# 15fpga.net
KiCad netlist of a schematic drawn in Altium Designer
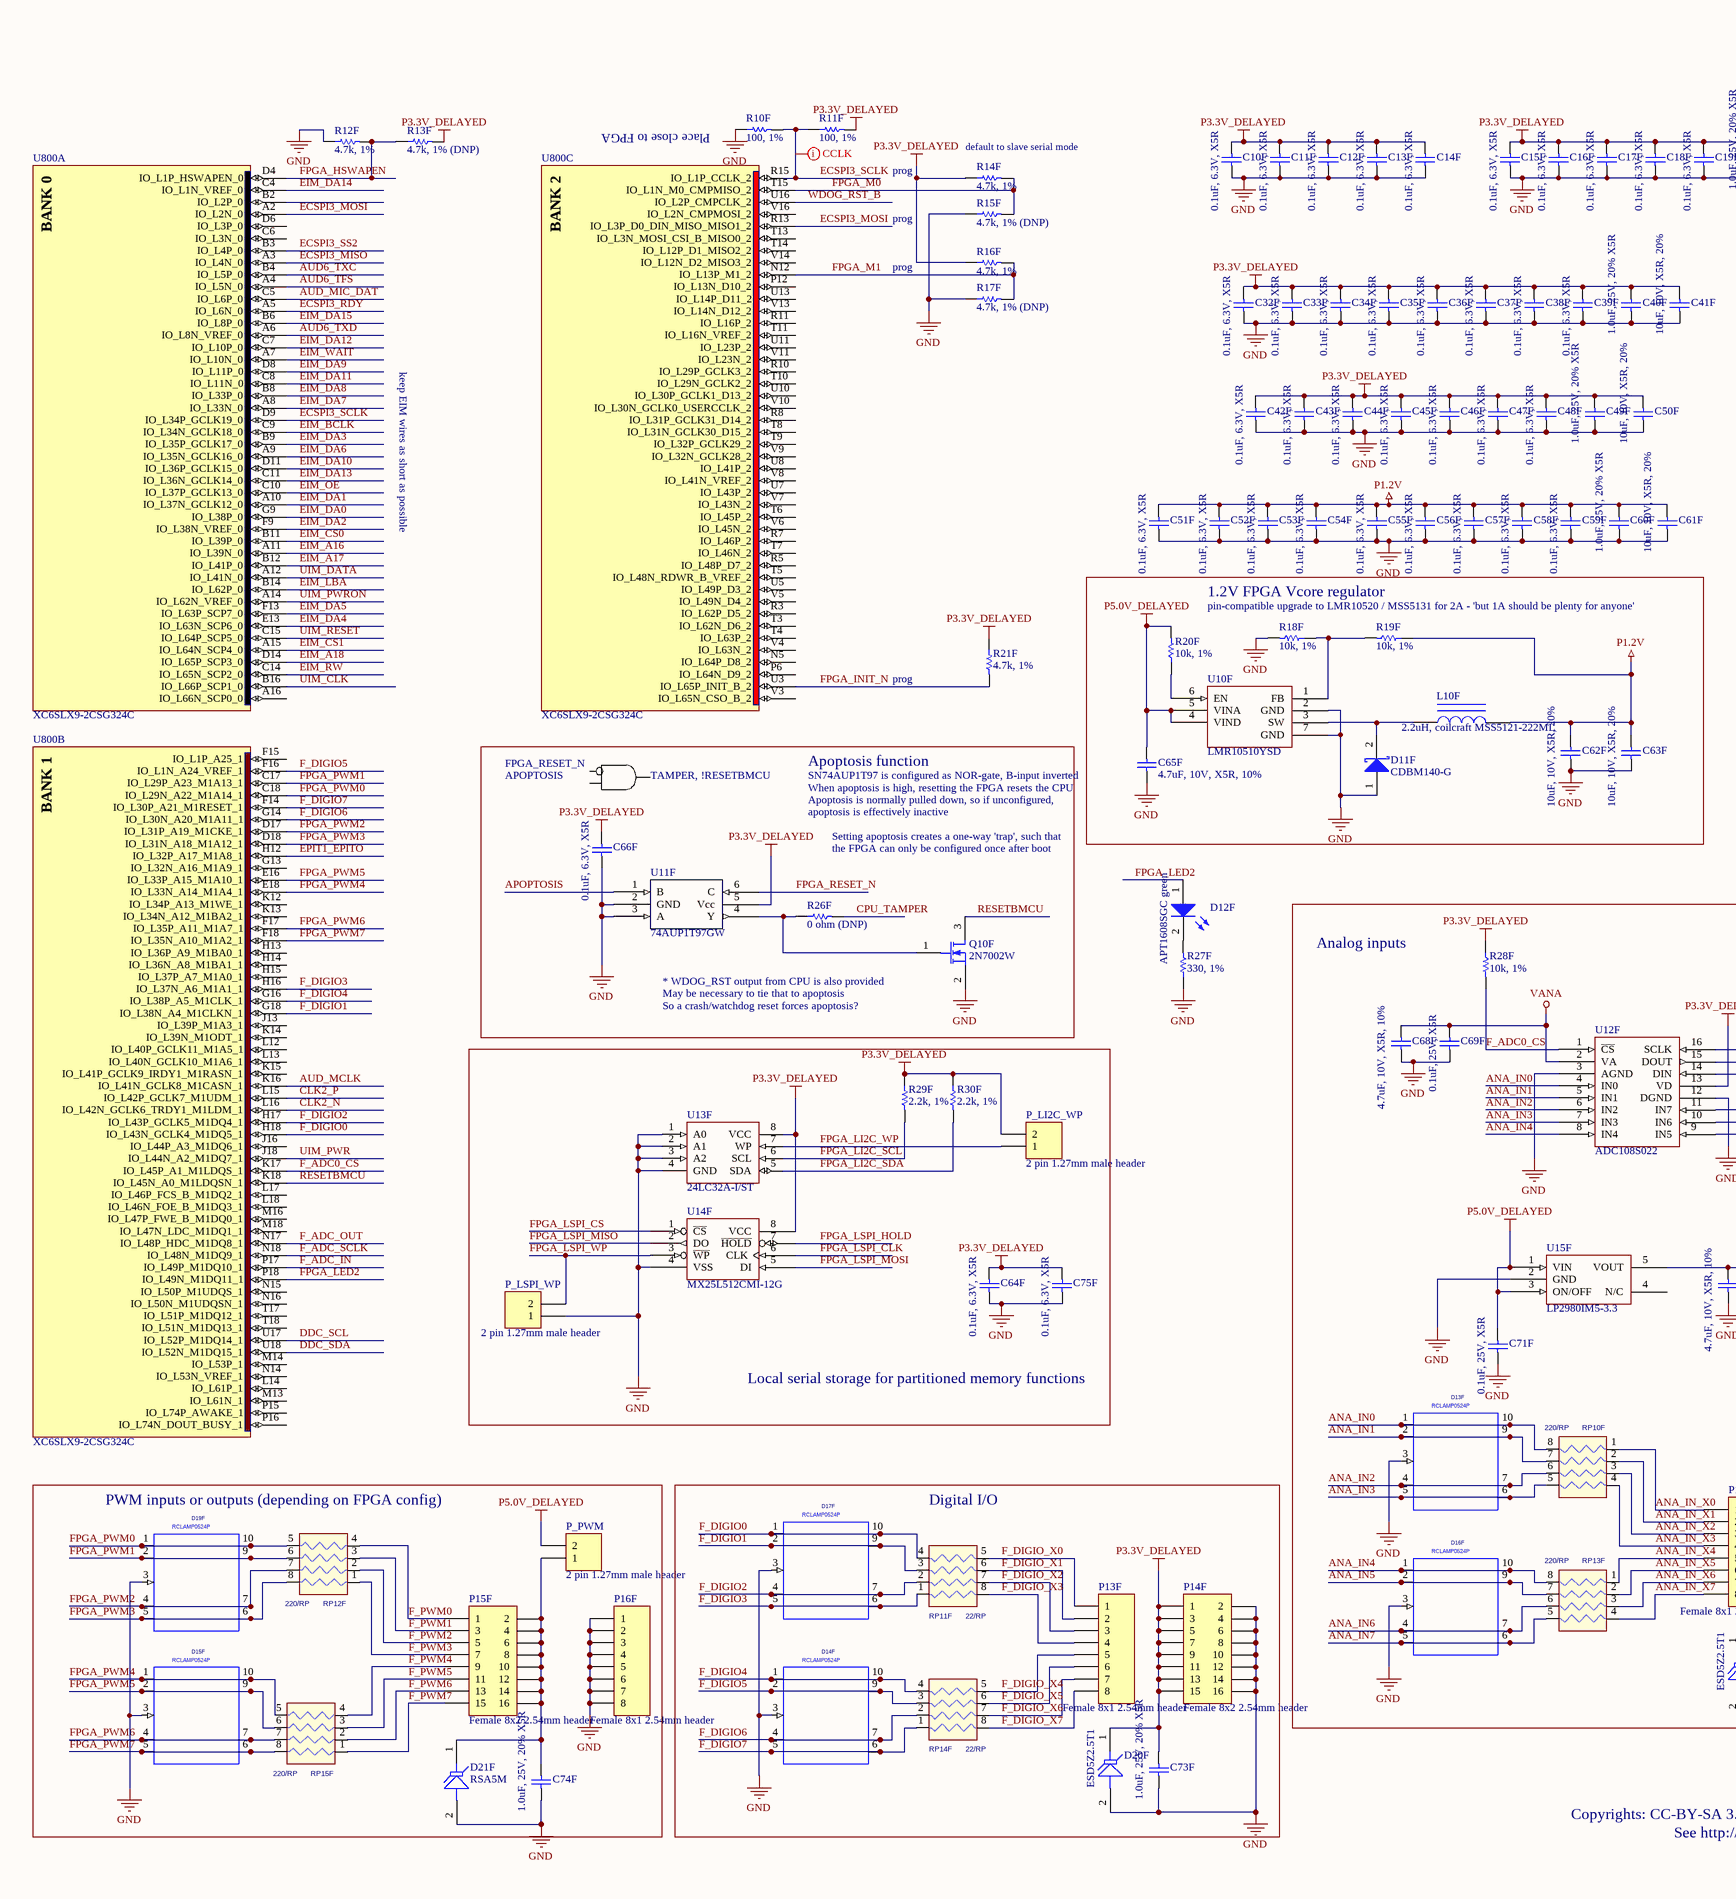
[diagram p0: 15fpga.SchDoc, left]
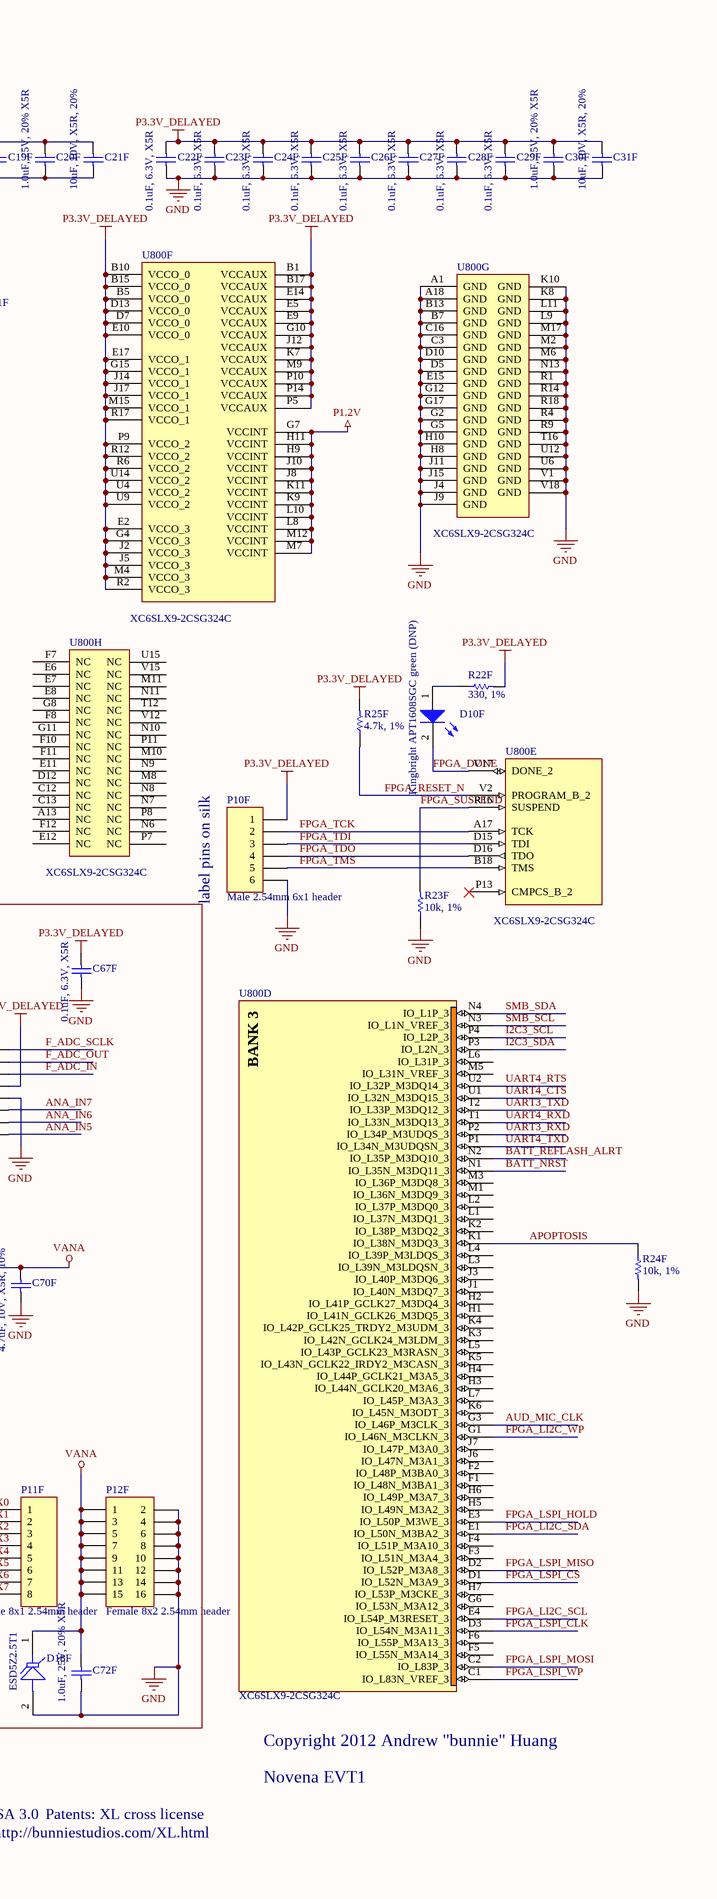
[diagram p1: 15fpga.SchDoc, right]

(export (version "E")
  (design (tool "Eeschema 10.0.6"))
  (components
    (comp (ref "C10F")
      (value "0.1uF, 6.3V, X5R")
      (footprint "CAPC0603N_B")
      (description "Capacitor (Semiconductor SIM Model)")
      (fields (field (name "PUBLISHER") "Altium Limited"))
      (libsource (lib "Miscellaneous Devices") (part "Cap Semi"))
    )
    (comp (ref "C11F")
      (value "0.1uF, 6.3V, X5R")
      (footprint "CAPC0603N_B")
      (description "Capacitor (Semiconductor SIM Model)")
      (fields (field (name "PUBLISHER") "Altium Limited"))
      (libsource (lib "Miscellaneous Devices") (part "Cap Semi"))
    )
    (comp (ref "C12F")
      (value "0.1uF, 6.3V, X5R")
      (footprint "CAPC0603N_B")
      (description "Capacitor (Semiconductor SIM Model)")
      (fields (field (name "PUBLISHER") "Altium Limited"))
      (libsource (lib "Miscellaneous Devices") (part "Cap Semi"))
    )
    (comp (ref "C13F")
      (value "0.1uF, 6.3V, X5R")
      (footprint "CAPC0603N_B")
      (description "Capacitor (Semiconductor SIM Model)")
      (fields (field (name "PUBLISHER") "Altium Limited"))
      (libsource (lib "Miscellaneous Devices") (part "Cap Semi"))
    )
    (comp (ref "C14F")
      (value "0.1uF, 6.3V, X5R")
      (footprint "CAPC0603N_B")
      (description "Capacitor (Semiconductor SIM Model)")
      (fields (field (name "PUBLISHER") "Altium Limited"))
      (libsource (lib "Miscellaneous Devices") (part "Cap Semi"))
    )
    (comp (ref "C15F")
      (value "0.1uF, 6.3V, X5R")
      (footprint "CAPC0603N_B")
      (description "Capacitor (Semiconductor SIM Model)")
      (fields (field (name "PUBLISHER") "Altium Limited"))
      (libsource (lib "Miscellaneous Devices") (part "Cap Semi"))
    )
    (comp (ref "C16F")
      (value "0.1uF, 6.3V, X5R")
      (footprint "CAPC0603N_B")
      (description "Capacitor (Semiconductor SIM Model)")
      (fields (field (name "PUBLISHER") "Altium Limited"))
      (libsource (lib "Miscellaneous Devices") (part "Cap Semi"))
    )
    (comp (ref "C17F")
      (value "0.1uF, 6.3V, X5R")
      (footprint "CAPC0603N_B")
      (description "Capacitor (Semiconductor SIM Model)")
      (fields (field (name "PUBLISHER") "Altium Limited"))
      (libsource (lib "Miscellaneous Devices") (part "Cap Semi"))
    )
    (comp (ref "C18F")
      (value "0.1uF, 6.3V, X5R")
      (footprint "CAPC0603N_B")
      (description "Capacitor (Semiconductor SIM Model)")
      (fields (field (name "PUBLISHER") "Altium Limited"))
      (libsource (lib "Miscellaneous Devices") (part "Cap Semi"))
    )
    (comp (ref "C19F")
      (value "0.1uF, 6.3V, X5R")
      (footprint "CAPC0603N_B")
      (description "Capacitor (Semiconductor SIM Model)")
      (fields (field (name "PUBLISHER") "Altium Limited"))
      (libsource (lib "Miscellaneous Devices") (part "Cap Semi"))
    )
    (comp (ref "C20F")
      (value "1.0uF, 25V, 20% X5R")
      (footprint "CAPC1608N")
      (description "Capacitor (Semiconductor SIM Model)")
      (fields (field (name "PUBLISHER") "Altium Limited"))
      (libsource (lib "Miscellaneous Devices") (part "Cap Semi"))
    )
    (comp (ref "C21F")
      (value "10uF, 10V, X5R, 20%")
      (footprint "CAPC1608N")
      (description "Capacitor (Semiconductor SIM Model)")
      (fields (field (name "PUBLISHER") "Altium Limited"))
      (libsource (lib "Miscellaneous Devices") (part "Cap Semi"))
    )
    (comp (ref "C22F")
      (value "0.1uF, 6.3V, X5R")
      (footprint "CAPC0603N_B")
      (description "Capacitor (Semiconductor SIM Model)")
      (fields (field (name "PUBLISHER") "Altium Limited"))
      (libsource (lib "Miscellaneous Devices") (part "Cap Semi"))
    )
    (comp (ref "C23F")
      (value "0.1uF, 6.3V, X5R")
      (footprint "CAPC0603N_B")
      (description "Capacitor (Semiconductor SIM Model)")
      (fields (field (name "PUBLISHER") "Altium Limited"))
      (libsource (lib "Miscellaneous Devices") (part "Cap Semi"))
    )
    (comp (ref "C24F")
      (value "0.1uF, 6.3V, X5R")
      (footprint "CAPC0603N_B")
      (description "Capacitor (Semiconductor SIM Model)")
      (fields (field (name "PUBLISHER") "Altium Limited"))
      (libsource (lib "Miscellaneous Devices") (part "Cap Semi"))
    )
    (comp (ref "C25F")
      (value "0.1uF, 6.3V, X5R")
      (footprint "CAPC0603N_B")
      (description "Capacitor (Semiconductor SIM Model)")
      (fields (field (name "PUBLISHER") "Altium Limited"))
      (libsource (lib "Miscellaneous Devices") (part "Cap Semi"))
    )
    (comp (ref "C26F")
      (value "0.1uF, 6.3V, X5R")
      (footprint "CAPC0603N_B")
      (description "Capacitor (Semiconductor SIM Model)")
      (fields (field (name "PUBLISHER") "Altium Limited"))
      (libsource (lib "Miscellaneous Devices") (part "Cap Semi"))
    )
    (comp (ref "C27F")
      (value "0.1uF, 6.3V, X5R")
      (footprint "CAPC0603N_B")
      (description "Capacitor (Semiconductor SIM Model)")
      (fields (field (name "PUBLISHER") "Altium Limited"))
      (libsource (lib "Miscellaneous Devices") (part "Cap Semi"))
    )
    (comp (ref "C28F")
      (value "0.1uF, 6.3V, X5R")
      (footprint "CAPC0603N_B")
      (description "Capacitor (Semiconductor SIM Model)")
      (fields (field (name "PUBLISHER") "Altium Limited"))
      (libsource (lib "Miscellaneous Devices") (part "Cap Semi"))
    )
    (comp (ref "C29F")
      (value "0.1uF, 6.3V, X5R")
      (footprint "CAPC0603N_B")
      (description "Capacitor (Semiconductor SIM Model)")
      (fields (field (name "PUBLISHER") "Altium Limited"))
      (libsource (lib "Miscellaneous Devices") (part "Cap Semi"))
    )
    (comp (ref "C30F")
      (value "1.0uF, 25V, 20% X5R")
      (footprint "CAPC1608N")
      (description "Capacitor (Semiconductor SIM Model)")
      (fields (field (name "PUBLISHER") "Altium Limited"))
      (libsource (lib "Miscellaneous Devices") (part "Cap Semi"))
    )
    (comp (ref "C31F")
      (value "10uF, 10V, X5R, 20%")
      (footprint "CAPC1608N")
      (description "Capacitor (Semiconductor SIM Model)")
      (fields (field (name "PUBLISHER") "Altium Limited"))
      (libsource (lib "Miscellaneous Devices") (part "Cap Semi"))
    )
    (comp (ref "C32F")
      (value "0.1uF, 6.3V, X5R")
      (footprint "CAPC0603N_B")
      (description "Capacitor (Semiconductor SIM Model)")
      (fields (field (name "PUBLISHER") "Altium Limited"))
      (libsource (lib "Miscellaneous Devices") (part "Cap Semi"))
    )
    (comp (ref "C33F")
      (value "0.1uF, 6.3V, X5R")
      (footprint "CAPC0603N_B")
      (description "Capacitor (Semiconductor SIM Model)")
      (fields (field (name "PUBLISHER") "Altium Limited"))
      (libsource (lib "Miscellaneous Devices") (part "Cap Semi"))
    )
    (comp (ref "C34F")
      (value "0.1uF, 6.3V, X5R")
      (footprint "CAPC0603N_B")
      (description "Capacitor (Semiconductor SIM Model)")
      (fields (field (name "PUBLISHER") "Altium Limited"))
      (libsource (lib "Miscellaneous Devices") (part "Cap Semi"))
    )
    (comp (ref "C35F")
      (value "0.1uF, 6.3V, X5R")
      (footprint "CAPC0603N_B")
      (description "Capacitor (Semiconductor SIM Model)")
      (fields (field (name "PUBLISHER") "Altium Limited"))
      (libsource (lib "Miscellaneous Devices") (part "Cap Semi"))
    )
    (comp (ref "C36F")
      (value "0.1uF, 6.3V, X5R")
      (footprint "CAPC0603N_B")
      (description "Capacitor (Semiconductor SIM Model)")
      (fields (field (name "PUBLISHER") "Altium Limited"))
      (libsource (lib "Miscellaneous Devices") (part "Cap Semi"))
    )
    (comp (ref "C37F")
      (value "0.1uF, 6.3V, X5R")
      (footprint "CAPC0603N_B")
      (description "Capacitor (Semiconductor SIM Model)")
      (fields (field (name "PUBLISHER") "Altium Limited"))
      (libsource (lib "Miscellaneous Devices") (part "Cap Semi"))
    )
    (comp (ref "C38F")
      (value "0.1uF, 6.3V, X5R")
      (footprint "CAPC0603N_B")
      (description "Capacitor (Semiconductor SIM Model)")
      (fields (field (name "PUBLISHER") "Altium Limited"))
      (libsource (lib "Miscellaneous Devices") (part "Cap Semi"))
    )
    (comp (ref "C39F")
      (value "0.1uF, 6.3V, X5R")
      (footprint "CAPC0603N_B")
      (description "Capacitor (Semiconductor SIM Model)")
      (fields (field (name "PUBLISHER") "Altium Limited"))
      (libsource (lib "Miscellaneous Devices") (part "Cap Semi"))
    )
    (comp (ref "C40F")
      (value "1.0uF, 25V, 20% X5R")
      (footprint "CAPC1608N")
      (description "Capacitor (Semiconductor SIM Model)")
      (fields (field (name "PUBLISHER") "Altium Limited"))
      (libsource (lib "Miscellaneous Devices") (part "Cap Semi"))
    )
    (comp (ref "C41F")
      (value "10uF, 10V, X5R, 20%")
      (footprint "CAPC1608N")
      (description "Capacitor (Semiconductor SIM Model)")
      (fields (field (name "PUBLISHER") "Altium Limited"))
      (libsource (lib "Miscellaneous Devices") (part "Cap Semi"))
    )
    (comp (ref "C42F")
      (value "0.1uF, 6.3V, X5R")
      (footprint "CAPC0603N_B")
      (description "Capacitor (Semiconductor SIM Model)")
      (fields (field (name "PUBLISHER") "Altium Limited"))
      (libsource (lib "Miscellaneous Devices") (part "Cap Semi"))
    )
    (comp (ref "C43F")
      (value "0.1uF, 6.3V, X5R")
      (footprint "CAPC0603N_B")
      (description "Capacitor (Semiconductor SIM Model)")
      (fields (field (name "PUBLISHER") "Altium Limited"))
      (libsource (lib "Miscellaneous Devices") (part "Cap Semi"))
    )
    (comp (ref "C44F")
      (value "0.1uF, 6.3V, X5R")
      (footprint "CAPC0603N_B")
      (description "Capacitor (Semiconductor SIM Model)")
      (fields (field (name "PUBLISHER") "Altium Limited"))
      (libsource (lib "Miscellaneous Devices") (part "Cap Semi"))
    )
    (comp (ref "C45F")
      (value "0.1uF, 6.3V, X5R")
      (footprint "CAPC0603N_B")
      (description "Capacitor (Semiconductor SIM Model)")
      (fields (field (name "PUBLISHER") "Altium Limited"))
      (libsource (lib "Miscellaneous Devices") (part "Cap Semi"))
    )
    (comp (ref "C46F")
      (value "0.1uF, 6.3V, X5R")
      (footprint "CAPC0603N_B")
      (description "Capacitor (Semiconductor SIM Model)")
      (fields (field (name "PUBLISHER") "Altium Limited"))
      (libsource (lib "Miscellaneous Devices") (part "Cap Semi"))
    )
    (comp (ref "C47F")
      (value "0.1uF, 6.3V, X5R")
      (footprint "CAPC0603N_B")
      (description "Capacitor (Semiconductor SIM Model)")
      (fields (field (name "PUBLISHER") "Altium Limited"))
      (libsource (lib "Miscellaneous Devices") (part "Cap Semi"))
    )
    (comp (ref "C48F")
      (value "0.1uF, 6.3V, X5R")
      (footprint "CAPC0603N_B")
      (description "Capacitor (Semiconductor SIM Model)")
      (fields (field (name "PUBLISHER") "Altium Limited"))
      (libsource (lib "Miscellaneous Devices") (part "Cap Semi"))
    )
    (comp (ref "C49F")
      (value "1.0uF, 25V, 20% X5R")
      (footprint "CAPC1608N")
      (description "Capacitor (Semiconductor SIM Model)")
      (fields (field (name "PUBLISHER") "Altium Limited"))
      (libsource (lib "Miscellaneous Devices") (part "Cap Semi"))
    )
    (comp (ref "C50F")
      (value "10uF, 10V, X5R, 20%")
      (footprint "CAPC1608N")
      (description "Capacitor (Semiconductor SIM Model)")
      (fields (field (name "PUBLISHER") "Altium Limited"))
      (libsource (lib "Miscellaneous Devices") (part "Cap Semi"))
    )
    (comp (ref "C51F")
      (value "0.1uF, 6.3V, X5R")
      (footprint "CAPC0603N_B")
      (description "Capacitor (Semiconductor SIM Model)")
      (fields (field (name "PUBLISHER") "Altium Limited"))
      (libsource (lib "Miscellaneous Devices") (part "Cap Semi"))
    )
    (comp (ref "C52F")
      (value "0.1uF, 6.3V, X5R")
      (footprint "CAPC0603N_B")
      (description "Capacitor (Semiconductor SIM Model)")
      (fields (field (name "PUBLISHER") "Altium Limited"))
      (libsource (lib "Miscellaneous Devices") (part "Cap Semi"))
    )
    (comp (ref "C53F")
      (value "0.1uF, 6.3V, X5R")
      (footprint "CAPC0603N_B")
      (description "Capacitor (Semiconductor SIM Model)")
      (fields (field (name "PUBLISHER") "Altium Limited"))
      (libsource (lib "Miscellaneous Devices") (part "Cap Semi"))
    )
    (comp (ref "C54F")
      (value "0.1uF, 6.3V, X5R")
      (footprint "CAPC0603N_B")
      (description "Capacitor (Semiconductor SIM Model)")
      (fields (field (name "PUBLISHER") "Altium Limited"))
      (libsource (lib "Miscellaneous Devices") (part "Cap Semi"))
    )
    (comp (ref "C55F")
      (value "0.1uF, 6.3V, X5R")
      (footprint "CAPC0603N_B")
      (description "Capacitor (Semiconductor SIM Model)")
      (fields (field (name "PUBLISHER") "Altium Limited"))
      (libsource (lib "Miscellaneous Devices") (part "Cap Semi"))
    )
    (comp (ref "C56F")
      (value "0.1uF, 6.3V, X5R")
      (footprint "CAPC0603N_B")
      (description "Capacitor (Semiconductor SIM Model)")
      (fields (field (name "PUBLISHER") "Altium Limited"))
      (libsource (lib "Miscellaneous Devices") (part "Cap Semi"))
    )
    (comp (ref "C57F")
      (value "0.1uF, 6.3V, X5R")
      (footprint "CAPC0603N_B")
      (description "Capacitor (Semiconductor SIM Model)")
      (fields (field (name "PUBLISHER") "Altium Limited"))
      (libsource (lib "Miscellaneous Devices") (part "Cap Semi"))
    )
    (comp (ref "C58F")
      (value "0.1uF, 6.3V, X5R")
      (footprint "CAPC0603N_B")
      (description "Capacitor (Semiconductor SIM Model)")
      (fields (field (name "PUBLISHER") "Altium Limited"))
      (libsource (lib "Miscellaneous Devices") (part "Cap Semi"))
    )
    (comp (ref "C59F")
      (value "0.1uF, 6.3V, X5R")
      (footprint "CAPC0603N_B")
      (description "Capacitor (Semiconductor SIM Model)")
      (fields (field (name "PUBLISHER") "Altium Limited"))
      (libsource (lib "Miscellaneous Devices") (part "Cap Semi"))
    )
    (comp (ref "C60F")
      (value "1.0uF, 25V, 20% X5R")
      (footprint "CAPC1608N")
      (description "Capacitor (Semiconductor SIM Model)")
      (fields (field (name "PUBLISHER") "Altium Limited"))
      (libsource (lib "Miscellaneous Devices") (part "Cap Semi"))
    )
    (comp (ref "C61F")
      (value "10uF, 10V, X5R, 20%")
      (footprint "CAPC1608N")
      (description "Capacitor (Semiconductor SIM Model)")
      (fields (field (name "PUBLISHER") "Altium Limited"))
      (libsource (lib "Miscellaneous Devices") (part "Cap Semi"))
    )
    (comp (ref "C62F")
      (value "10uF, 10V, X5R, 20%")
      (footprint "CAPC1608N")
      (description "Capacitor (Semiconductor SIM Model)")
      (fields (field (name "PUBLISHER") "Altium Limited"))
      (libsource (lib "Miscellaneous Devices") (part "Cap Semi"))
    )
    (comp (ref "C63F")
      (value "10uF, 10V, X5R, 20%")
      (footprint "CAPC1608N")
      (description "Capacitor (Semiconductor SIM Model)")
      (fields (field (name "PUBLISHER") "Altium Limited"))
      (libsource (lib "Miscellaneous Devices") (part "Cap Semi"))
    )
    (comp (ref "C64F")
      (value "0.1uF, 6.3V, X5R")
      (footprint "CAPC0603N_B")
      (description "Capacitor (Semiconductor SIM Model)")
      (fields (field (name "PUBLISHER") "Altium Limited"))
      (libsource (lib "Miscellaneous Devices") (part "Cap Semi"))
    )
    (comp (ref "C65F")
      (value "4.7uF, 10V, X5R, 10%")
      (footprint "CAPC1608N")
      (description "Capacitor (Semiconductor SIM Model)")
      (fields (field (name "PUBLISHER") "Altium Limited"))
      (libsource (lib "Miscellaneous Devices") (part "Cap Semi"))
    )
    (comp (ref "C66F")
      (value "0.1uF, 6.3V, X5R")
      (footprint "CAPC0603N_B")
      (description "Capacitor (Semiconductor SIM Model)")
      (fields (field (name "PUBLISHER") "Altium Limited"))
      (libsource (lib "Miscellaneous Devices") (part "Cap Semi"))
    )
    (comp (ref "C67F")
      (value "0.1uF, 6.3V, X5R")
      (footprint "CAPC0603N_B")
      (description "Capacitor (Semiconductor SIM Model)")
      (fields (field (name "PUBLISHER") "Altium Limited"))
      (libsource (lib "Miscellaneous Devices") (part "Cap Semi"))
    )
    (comp (ref "C68F")
      (value "4.7uF, 10V, X5R, 10%")
      (footprint "CAPC1608N")
      (description "Capacitor (Semiconductor SIM Model)")
      (fields (field (name "PUBLISHER") "Altium Limited"))
      (libsource (lib "Miscellaneous Devices") (part "Cap Semi"))
    )
    (comp (ref "C69F")
      (value "0.1uF, 25V, X5R")
      (footprint "CAPC1005N")
      (description "Capacitor (Semiconductor SIM Model)")
      (fields (field (name "PUBLISHER") "Altium Limited"))
      (libsource (lib "Miscellaneous Devices") (part "Cap Semi"))
    )
    (comp (ref "C70F")
      (value "4.7uF, 10V, X5R, 10%")
      (footprint "CAPC1608N")
      (description "Capacitor (Semiconductor SIM Model)")
      (fields (field (name "PUBLISHER") "Altium Limited"))
      (libsource (lib "Miscellaneous Devices") (part "Cap Semi"))
    )
    (comp (ref "C71F")
      (value "0.1uF, 25V, X5R")
      (footprint "CAPC1005N")
      (description "Capacitor (Semiconductor SIM Model)")
      (fields (field (name "PUBLISHER") "Altium Limited"))
      (libsource (lib "Miscellaneous Devices") (part "Cap Semi"))
    )
    (comp (ref "C72F")
      (value "1.0uF, 25V, 20% X5R")
      (footprint "CAPC1608N")
      (description "Capacitor (Semiconductor SIM Model)")
      (fields (field (name "PUBLISHER") "Altium Limited"))
      (libsource (lib "Miscellaneous Devices") (part "Cap Semi"))
    )
    (comp (ref "C73F")
      (value "1.0uF, 25V, 20% X5R")
      (footprint "CAPC1608N")
      (description "Capacitor (Semiconductor SIM Model)")
      (fields (field (name "PUBLISHER") "Altium Limited"))
      (libsource (lib "Miscellaneous Devices") (part "Cap Semi"))
    )
    (comp (ref "C74F")
      (value "1.0uF, 25V, 20% X5R")
      (footprint "CAPC1608N")
      (description "Capacitor (Semiconductor SIM Model)")
      (fields (field (name "PUBLISHER") "Altium Limited"))
      (libsource (lib "Miscellaneous Devices") (part "Cap Semi"))
    )
    (comp (ref "C75F")
      (value "0.1uF, 6.3V, X5R")
      (footprint "CAPC0603N_B")
      (description "Capacitor (Semiconductor SIM Model)")
      (fields (field (name "PUBLISHER") "Altium Limited"))
      (libsource (lib "Miscellaneous Devices") (part "Cap Semi"))
    )
    (comp (ref "D10F")
      (value "Kingbright APT1608SGC green (DNP)")
      (footprint "CD1608-0603")
      (description "Typical RED, GREEN, YELLOW, AMBER GaAs LED")
      (fields (field (name "PUBLISHER") "Altium Limited"))
      (libsource (lib "Miscellaneous Devices") (part "LED2"))
    )
    (comp (ref "D11F")
      (value "CDBM140-G")
      (footprint "SOD123")
      (description "Schottky Diode")
      (fields (field (name "PUBLISHER") "Altium Limited"))
      (libsource (lib "Miscellaneous Devices") (part "D Schottky"))
    )
    (comp (ref "D12F")
      (value "APT1608SGC green")
      (footprint "CD1608-0603")
      (description "Typical RED, GREEN, YELLOW, AMBER GaAs LED")
      (fields (field (name "PUBLISHER") "Altium Limited"))
      (libsource (lib "Miscellaneous Devices") (part "LED2"))
    )
    (comp (ref "D13F")
      (value "RCLAMP0524P")
      (fields (field (name "PART_NUMBER") "V00004-001"))
      (libsource (lib "*") (part "RCLAMP0524P"))
    )
    (comp (ref "D14F")
      (value "RCLAMP0524P")
      (fields (field (name "PART_NUMBER") "V00004-001"))
      (libsource (lib "*") (part "RCLAMP0524P"))
    )
    (comp (ref "D15F")
      (value "RCLAMP0524P")
      (fields (field (name "PART_NUMBER") "V00004-001"))
      (libsource (lib "*") (part "RCLAMP0524P"))
    )
    (comp (ref "D16F")
      (value "RCLAMP0524P")
      (fields (field (name "PART_NUMBER") "V00004-001"))
      (libsource (lib "*") (part "RCLAMP0524P"))
    )
    (comp (ref "D17F")
      (value "RCLAMP0524P")
      (fields (field (name "PART_NUMBER") "V00004-001"))
      (libsource (lib "*") (part "RCLAMP0524P"))
    )
    (comp (ref "D18F")
      (value "ESD5Z2.5T1")
      (footprint "SOD-523")
      (description "On Semi 3.3V standoff TVS diode")
      (fields (field (name "PUBLISHER") "Altium Limited"))
      (libsource (lib "Miscellaneous Devices") (part "Tranzorb"))
    )
    (comp (ref "D19F")
      (value "RCLAMP0524P")
      (fields (field (name "PART_NUMBER") "V00004-001"))
      (libsource (lib "*") (part "RCLAMP0524P"))
    )
    (comp (ref "D20F")
      (value "ESD5Z2.5T1")
      (footprint "SOD-523")
      (description "On Semi 3.3V standoff TVS diode")
      (fields (field (name "PUBLISHER") "Altium Limited"))
      (libsource (lib "Miscellaneous Devices") (part "Tranzorb"))
    )
    (comp (ref "D21F")
      (value "RSA5M")
      (footprint "SOD123/X.85")
      (description "Tranzorb")
      (fields (field (name "PUBLISHER") "Altium Limited"))
      (libsource (lib "Miscellaneous Devices") (part "Tranzorb"))
    )
    (comp (ref "L10F")
      (value "2.2uH, coilcraft MSS5121-222ML")
      (footprint "COILCRAFT_MSS5121")
      (description "Magnetic-Core Inductor")
      (fields (field (name "PUBLISHER") "Altium Limited"))
      (libsource (lib "Miscellaneous Devices") (part "Inductor Iron"))
    )
    (comp (ref "P10F")
      (value "Male 2.54mm 6x1 header")
      (footprint "HDR1X6")
      (description "Header, 6-Pin")
      (fields (field (name "PUBLISHER") "Altium Limited"))
      (libsource (lib "Miscellaneous Connectors") (part "Header 6"))
    )
    (comp (ref "P11F")
      (value "Female 8x1 2.54mm header")
      (footprint "HDR1X8")
      (description "Header, 8-Pin")
      (fields (field (name "PUBLISHER") "Altium Limited"))
      (libsource (lib "Miscellaneous Connectors") (part "Header 8"))
    )
    (comp (ref "P12F")
      (value "Female 8x2 2.54mm header")
      (footprint "HDR2X8")
      (description "Header, 8-Pin, Dual row")
      (fields (field (name "PUBLISHER") "Altium Limited"))
      (libsource (lib "Miscellaneous Connectors") (part "Header 8X2"))
    )
    (comp (ref "P13F")
      (value "Female 8x1 2.54mm header")
      (footprint "HDR1X8")
      (description "Header, 8-Pin")
      (fields (field (name "PUBLISHER") "Altium Limited"))
      (libsource (lib "Miscellaneous Connectors") (part "Header 8"))
    )
    (comp (ref "P14F")
      (value "Female 8x2 2.54mm header")
      (footprint "HDR2X8")
      (description "Header, 8-Pin, Dual row")
      (fields (field (name "PUBLISHER") "Altium Limited"))
      (libsource (lib "Miscellaneous Connectors") (part "Header 8X2"))
    )
    (comp (ref "P15F")
      (value "Female 8x2 2.54mm header")
      (footprint "HDR2X8")
      (description "Header, 8-Pin, Dual row")
      (fields (field (name "PUBLISHER") "Altium Limited"))
      (libsource (lib "Miscellaneous Connectors") (part "Header 8X2"))
    )
    (comp (ref "P16F")
      (value "Female 8x1 2.54mm header")
      (footprint "HDR1X8")
      (description "Header, 8-Pin")
      (fields (field (name "PUBLISHER") "Altium Limited"))
      (libsource (lib "Miscellaneous Connectors") (part "Header 8"))
    )
    (comp (ref "P_LI2C_WP")
      (value "2 pin 1.27mm male header")
      (footprint "HEADER_2_1.27MM")
      (description "Header, 2-Pin")
      (fields (field (name "PUBLISHER") "Altium Limited"))
      (libsource (lib "Miscellaneous Connectors") (part "Header 2"))
    )
    (comp (ref "P_LSPI_WP")
      (value "2 pin 1.27mm male header")
      (footprint "HEADER_2_1.27MM")
      (description "Header, 2-Pin")
      (fields (field (name "PUBLISHER") "Altium Limited"))
      (libsource (lib "") (part "Header 2_1"))
    )
    (comp (ref "P_PWM")
      (value "2 pin 1.27mm male header")
      (footprint "HEADER_2_1.27MM")
      (description "Header, 2-Pin")
      (fields (field (name "PUBLISHER") "Altium Limited"))
      (libsource (lib "Miscellaneous Connectors") (part "Header 2"))
    )
    (comp (ref "Q10F")
      (value "2N7002W")
      (footprint "SOT323-3AN")
      (description "N-Channel MOSFET")
      (fields (field (name "PUBLISHER") "Altium Limited"))
      (libsource (lib "Miscellaneous Devices") (part "MOSFET-N"))
    )
    (comp (ref "R10F")
      (value "100, 1%")
      (footprint "RESC1005N")
      (description "Resistor")
      (fields (field (name "PUBLISHER") "Altium Limited"))
      (libsource (lib "Miscellaneous Devices") (part "Res1"))
    )
    (comp (ref "R11F")
      (value "100, 1%")
      (footprint "RESC1005N")
      (description "Resistor")
      (fields (field (name "PUBLISHER") "Altium Limited"))
      (libsource (lib "Miscellaneous Devices") (part "Res1"))
    )
    (comp (ref "R12F")
      (value "4.7k, 1%")
      (footprint "RESC1005N")
      (description "Resistor")
      (fields (field (name "PUBLISHER") "Altium Limited"))
      (libsource (lib "Miscellaneous Devices") (part "Res1"))
    )
    (comp (ref "R13F")
      (value "4.7k, 1% (DNP)")
      (footprint "RESC1005N")
      (description "Resistor")
      (fields (field (name "PUBLISHER") "Altium Limited"))
      (libsource (lib "Miscellaneous Devices") (part "Res1"))
    )
    (comp (ref "R14F")
      (value "4.7k, 1%")
      (footprint "RESC1005N")
      (description "Resistor")
      (fields (field (name "PUBLISHER") "Altium Limited"))
      (libsource (lib "Miscellaneous Devices") (part "Res1"))
    )
    (comp (ref "R15F")
      (value "4.7k, 1% (DNP)")
      (footprint "RESC1005N")
      (description "Resistor")
      (fields (field (name "PUBLISHER") "Altium Limited"))
      (libsource (lib "Miscellaneous Devices") (part "Res1"))
    )
    (comp (ref "R16F")
      (value "4.7k, 1%")
      (footprint "RESC1005N")
      (description "Resistor")
      (fields (field (name "PUBLISHER") "Altium Limited"))
      (libsource (lib "Miscellaneous Devices") (part "Res1"))
    )
    (comp (ref "R17F")
      (value "4.7k, 1% (DNP)")
      (footprint "RESC1005N")
      (description "Resistor")
      (fields (field (name "PUBLISHER") "Altium Limited"))
      (libsource (lib "Miscellaneous Devices") (part "Res1"))
    )
    (comp (ref "R18F")
      (value "10k, 1%")
      (footprint "RESC1005N")
      (description "Resistor")
      (fields (field (name "PUBLISHER") "Altium Limited"))
      (libsource (lib "Miscellaneous Devices") (part "Res1"))
    )
    (comp (ref "R19F")
      (value "10k, 1%")
      (footprint "RESC1005N")
      (description "Resistor")
      (fields (field (name "PUBLISHER") "Altium Limited"))
      (libsource (lib "Miscellaneous Devices") (part "Res1"))
    )
    (comp (ref "R20F")
      (value "10k, 1%")
      (footprint "RESC1005N")
      (description "Resistor")
      (fields (field (name "PUBLISHER") "Altium Limited"))
      (libsource (lib "Miscellaneous Devices") (part "Res1"))
    )
    (comp (ref "R21F")
      (value "4.7k, 1%")
      (footprint "RESC1005N")
      (description "Resistor")
      (fields (field (name "PUBLISHER") "Altium Limited"))
      (libsource (lib "Miscellaneous Devices") (part "Res1"))
    )
    (comp (ref "R22F")
      (value "330, 1%")
      (footprint "RESC1005N")
      (description "Resistor")
      (fields (field (name "PUBLISHER") "Altium Limited"))
      (libsource (lib "Miscellaneous Devices") (part "Res1"))
    )
    (comp (ref "R23F")
      (value "10k, 1%")
      (footprint "RESC1005N")
      (description "Resistor")
      (fields (field (name "PUBLISHER") "Altium Limited"))
      (libsource (lib "Miscellaneous Devices") (part "Res1"))
    )
    (comp (ref "R24F")
      (value "10k, 1%")
      (footprint "RESC1005N")
      (description "Resistor")
      (fields (field (name "PUBLISHER") "Altium Limited"))
      (libsource (lib "Miscellaneous Devices") (part "Res1"))
    )
    (comp (ref "R25F")
      (value "4.7k, 1%")
      (footprint "RESC1005N")
      (description "Resistor")
      (fields (field (name "PUBLISHER") "Altium Limited"))
      (libsource (lib "Miscellaneous Devices") (part "Res1"))
    )
    (comp (ref "R26F")
      (value "0 ohm (DNP)")
      (footprint "RESC1005N")
      (description "Resistor")
      (fields (field (name "PUBLISHER") "Altium Limited"))
      (libsource (lib "Miscellaneous Devices") (part "Res1"))
    )
    (comp (ref "R27F")
      (value "330, 1%")
      (footprint "RESC1005N")
      (description "Resistor")
      (fields (field (name "PUBLISHER") "Altium Limited"))
      (libsource (lib "Miscellaneous Devices") (part "Res1"))
    )
    (comp (ref "R28F")
      (value "10k, 1%")
      (footprint "RESC1005N")
      (description "Resistor")
      (fields (field (name "PUBLISHER") "Altium Limited"))
      (libsource (lib "Miscellaneous Devices") (part "Res1"))
    )
    (comp (ref "R29F")
      (value "2.2k, 1%")
      (footprint "RESC1005N")
      (description "Resistor")
      (fields (field (name "PUBLISHER") "Altium Limited"))
      (libsource (lib "Miscellaneous Devices") (part "Res1"))
    )
    (comp (ref "R30F")
      (value "2.2k, 1%")
      (footprint "RESC1005N")
      (description "Resistor")
      (fields (field (name "PUBLISHER") "Altium Limited"))
      (libsource (lib "Miscellaneous Devices") (part "Res1"))
    )
    (comp (ref "RP10F") (value "220/RP") (libsource (lib "*") (part "RPACK4")))
    (comp (ref "RP11F") (value "22/RP") (libsource (lib "*") (part "RPACK4")))
    (comp (ref "RP12F") (value "220/RP") (libsource (lib "*") (part "RPACK4")))
    (comp (ref "RP13F") (value "220/RP") (libsource (lib "*") (part "RPACK4")))
    (comp (ref "RP14F") (value "22/RP") (libsource (lib "*") (part "RPACK4")))
    (comp (ref "RP15F") (value "220/RP") (libsource (lib "*") (part "RPACK4")))
    (comp (ref "U10F")
      (value "LMR10510YSD")
      (footprint "SON95P300X300X80-7V")
      (description "NatSemi 1.5A step-down regulator in LLP")
      (libsource (lib "commonsch") (part "LMR10515XSD"))
    )
    (comp (ref "U11F")
      (value "74AUP1T97GW")
      (footprint "SOT363-6N")
      (description "Single-supply voltage translator, multiple logic function")
      (libsource (lib "*") (part "SN74AUP1T98DBV"))
    )
    (comp (ref "U12F")
      (value "ADC108S022")
      (footprint "SOP65P640-16N")
      (description "12-input SPI ADC, bits & sample rate pin compatible across family")
      (libsource (lib "commonsch") (part "ADCxx8Sxx2"))
    )
    (comp (ref "U13F")
      (value "24LC32A-I/ST")
      (footprint "TSOP65P640-8AN")
      (description "8kbit (1kx8) I2C EEPROM")
      (libsource (lib "*") (part "AT24C08"))
    )
    (comp (ref "U14F")
      (value "MX25L512CMI-12G")
      (footprint "SOIC127P600-8AN")
      (description "512 Mbit (64Kbyte) SPI NOR FLASH, Eon Semi")
      (libsource (lib "commonsch") (part "EN25P05-50GCP"))
    )
    (comp (ref "U15F")
      (value "LP2980IM5-3.3")
      (footprint "SOT23-5AN")
      (description "50 mA SOT-23 regulator")
      (libsource (lib "commonsch") (part "LP2980M5"))
    )
    (comp (ref "U800")
      (value "XC6SLX9-2CSG324C")
      (footprint "CSG324")
      (fields (field (name "PUBLISHER") "Altium Limited"))
      (libsource (lib "Xilinx Spartan-6") (part "XC6SLX9-2CSG324C"))
    )
  )
  (nets
    (net (code "1") (name "/ANA_IN0") (class "Default")
      (node (ref "D13F") (pin "1") (pinfunction "IO1A_1") (pintype "bidirectional"))
      (node (ref "D13F") (pin "10") (pinfunction "IO1B_10") (pintype "bidirectional"))
      (node (ref "RP10F") (pin "8") (pinfunction "R12_8") (pintype "passive"))
      (node (ref "U12F") (pin "4") (pinfunction "IN0_4") (pintype "input"))
    )
    (net (code "2") (name "/ANA_IN1") (class "Default")
      (node (ref "D13F") (pin "2") (pinfunction "IO2A_2") (pintype "bidirectional"))
      (node (ref "D13F") (pin "9") (pinfunction "IO2B_9") (pintype "bidirectional"))
      (node (ref "RP10F") (pin "7") (pinfunction "R22_7") (pintype "passive"))
      (node (ref "U12F") (pin "5") (pinfunction "IN1_5") (pintype "input"))
    )
    (net (code "3") (name "/ANA_IN2") (class "Default")
      (node (ref "D13F") (pin "4") (pinfunction "IO3A_4") (pintype "bidirectional"))
      (node (ref "D13F") (pin "7") (pinfunction "IO3B_7") (pintype "bidirectional"))
      (node (ref "RP10F") (pin "6") (pinfunction "R32_6") (pintype "passive"))
      (node (ref "U12F") (pin "6") (pinfunction "IN2_6") (pintype "input"))
    )
    (net (code "4") (name "/ANA_IN3") (class "Default")
      (node (ref "D13F") (pin "5") (pinfunction "IO4A_5") (pintype "bidirectional"))
      (node (ref "D13F") (pin "6") (pinfunction "IO4B_6") (pintype "bidirectional"))
      (node (ref "RP10F") (pin "5") (pinfunction "R42_5") (pintype "passive"))
      (node (ref "U12F") (pin "7") (pinfunction "IN3_7") (pintype "input"))
    )
    (net (code "5") (name "/ANA_IN4") (class "Default")
      (node (ref "D16F") (pin "1") (pinfunction "IO1A_1") (pintype "bidirectional"))
      (node (ref "D16F") (pin "10") (pinfunction "IO1B_10") (pintype "bidirectional"))
      (node (ref "RP13F") (pin "8") (pinfunction "R12_8") (pintype "passive"))
      (node (ref "U12F") (pin "8") (pinfunction "IN4_8") (pintype "input"))
    )
    (net (code "6") (name "/ANA_IN5") (class "Default")
      (node (ref "D16F") (pin "2") (pinfunction "IO2A_2") (pintype "bidirectional"))
      (node (ref "D16F") (pin "9") (pinfunction "IO2B_9") (pintype "bidirectional"))
      (node (ref "RP13F") (pin "7") (pinfunction "R22_7") (pintype "passive"))
      (node (ref "U12F") (pin "9") (pinfunction "IN5_9") (pintype "input"))
    )
    (net (code "7") (name "/ANA_IN6") (class "Default")
      (node (ref "D16F") (pin "4") (pinfunction "IO3A_4") (pintype "bidirectional"))
      (node (ref "D16F") (pin "7") (pinfunction "IO3B_7") (pintype "bidirectional"))
      (node (ref "RP13F") (pin "6") (pinfunction "R32_6") (pintype "passive"))
      (node (ref "U12F") (pin "10") (pinfunction "IN6_10") (pintype "input"))
    )
    (net (code "8") (name "/ANA_IN7") (class "Default")
      (node (ref "D16F") (pin "5") (pinfunction "IO4A_5") (pintype "bidirectional"))
      (node (ref "D16F") (pin "6") (pinfunction "IO4B_6") (pintype "bidirectional"))
      (node (ref "RP13F") (pin "5") (pinfunction "R42_5") (pintype "passive"))
      (node (ref "U12F") (pin "11") (pinfunction "IN7_11") (pintype "input"))
    )
    (net (code "9") (name "/ANA_IN_X0") (class "Default")
      (node (ref "P11F") (pin "1") (pinfunction "1_1") (pintype "passive"))
      (node (ref "RP10F") (pin "1") (pinfunction "R1_1") (pintype "passive"))
    )
    (net (code "10") (name "/ANA_IN_X1") (class "Default")
      (node (ref "P11F") (pin "2") (pinfunction "2_2") (pintype "passive"))
      (node (ref "RP10F") (pin "2") (pinfunction "R2_2") (pintype "passive"))
    )
    (net (code "11") (name "/ANA_IN_X2") (class "Default")
      (node (ref "P11F") (pin "3") (pinfunction "3_3") (pintype "passive"))
      (node (ref "RP10F") (pin "3") (pinfunction "R3_3") (pintype "passive"))
    )
    (net (code "12") (name "/ANA_IN_X3") (class "Default")
      (node (ref "P11F") (pin "4") (pinfunction "4_4") (pintype "passive"))
      (node (ref "RP10F") (pin "4") (pinfunction "R4_4") (pintype "passive"))
    )
    (net (code "13") (name "/ANA_IN_X4") (class "Default")
      (node (ref "P11F") (pin "5") (pinfunction "5_5") (pintype "passive"))
      (node (ref "RP13F") (pin "1") (pinfunction "R1_1") (pintype "passive"))
    )
    (net (code "14") (name "/ANA_IN_X5") (class "Default")
      (node (ref "P11F") (pin "6") (pinfunction "6_6") (pintype "passive"))
      (node (ref "RP13F") (pin "2") (pinfunction "R2_2") (pintype "passive"))
    )
    (net (code "15") (name "/ANA_IN_X6") (class "Default")
      (node (ref "P11F") (pin "7") (pinfunction "7_7") (pintype "passive"))
      (node (ref "RP13F") (pin "3") (pinfunction "R3_3") (pintype "passive"))
    )
    (net (code "16") (name "/ANA_IN_X7") (class "Default")
      (node (ref "P11F") (pin "8") (pinfunction "8_8") (pintype "passive"))
      (node (ref "RP13F") (pin "4") (pinfunction "R4_4") (pintype "passive"))
    )
    (net (code "17") (name "/APOPTOSIS") (class "Default")
      (node (ref "R24F") (pin "1") (pinfunction "1_1") (pintype "passive"))
      (node (ref "U11F") (pin "1") (pinfunction "B_1") (pintype "input"))
      (node (ref "U800") (pin "K1") (pinfunction "IO_L38N_M3DQ3_3_K1") (pintype "bidirectional"))
    )
    (net (code "18") (name "/AUD6_TFS") (class "Default")
      (node (ref "U800") (pin "A4") (pinfunction "IO_L5N_0_A4") (pintype "bidirectional"))
    )
    (net (code "19") (name "/AUD6_TXC") (class "Default")
      (node (ref "U800") (pin "B4") (pinfunction "IO_L5P_0_B4") (pintype "bidirectional"))
    )
    (net (code "20") (name "/AUD6_TXD") (class "Default")
      (node (ref "U800") (pin "A6") (pinfunction "IO_L8N_VREF_0_A6") (pintype "bidirectional"))
    )
    (net (code "21") (name "/AUD_MCLK") (class "Default")
      (node (ref "U800") (pin "K16") (pinfunction "IO_L41N_GCLK8_M1CASN_1_K16") (pintype "bidirectional"))
    )
    (net (code "22") (name "/AUD_MIC_CLK") (class "Default")
      (node (ref "U800") (pin "G3") (pinfunction "IO_L46P_M3CLK_3_G3") (pintype "bidirectional"))
    )
    (net (code "23") (name "/AUD_MIC_DAT") (class "Default")
      (node (ref "U800") (pin "C5") (pinfunction "IO_L6P_0_C5") (pintype "bidirectional"))
    )
    (net (code "24") (name "/BATT_NRST") (class "Default")
      (node (ref "U800") (pin "N1") (pinfunction "IO_L35N_M3DQ11_3_N1") (pintype "bidirectional"))
    )
    (net (code "25") (name "/BATT_REFLASH_ALRT") (class "Default")
      (node (ref "U800") (pin "N2") (pinfunction "IO_L35P_M3DQ10_3_N2") (pintype "bidirectional"))
    )
    (net (code "26") (name "/CLK2_N") (class "Default")
      (node (ref "U800") (pin "L16") (pinfunction "IO_L42N_GCLK6_TRDY1_M1LDM_1_L16") (pintype "bidirectional"))
    )
    (net (code "27") (name "/CLK2_P") (class "Default")
      (node (ref "U800") (pin "L15") (pinfunction "IO_L42P_GCLK7_M1UDM_1_L15") (pintype "bidirectional"))
    )
    (net (code "28") (name "/CPU_TAMPER") (class "Default")
      (node (ref "R26F") (pin "2") (pinfunction "2_2") (pintype "passive"))
    )
    (net (code "29") (name "/DDC_SCL") (class "Default")
      (node (ref "U800") (pin "U17") (pinfunction "IO_L52P_M1DQ14_1_U17") (pintype "bidirectional"))
    )
    (net (code "30") (name "/DDC_SDA") (class "Default")
      (node (ref "U800") (pin "U18") (pinfunction "IO_L52N_M1DQ15_1_U18") (pintype "bidirectional"))
    )
    (net (code "31") (name "/ECSPI3_MISO") (class "Default")
      (node (ref "U800") (pin "A3") (pinfunction "IO_L4N_0_A3") (pintype "bidirectional"))
    )
    (net (code "32") (name "/ECSPI3_MOSI") (class "Default")
      (node (ref "U800") (pin "A2") (pinfunction "IO_L2N_0_A2") (pintype "bidirectional"))
      (node (ref "U800") (pin "R13") (pinfunction "IO_L3P_D0_DIN_MISO_MISO1_2_R13") (pintype "bidirectional"))
    )
    (net (code "33") (name "/ECSPI3_RDY") (class "Default")
      (node (ref "U800") (pin "A5") (pinfunction "IO_L6N_0_A5") (pintype "bidirectional"))
    )
    (net (code "34") (name "/ECSPI3_SCLK") (class "Default")
      (node (ref "R10F") (pin "2") (pinfunction "2_2") (pintype "passive"))
      (node (ref "R11F") (pin "1") (pinfunction "1_1") (pintype "passive"))
      (node (ref "U800") (pin "D9") (pinfunction "IO_L34P_GCLK19_0_D9") (pintype "bidirectional"))
      (node (ref "U800") (pin "R15") (pinfunction "IO_L1P_CCLK_2_R15") (pintype "bidirectional"))
    )
    (net (code "35") (name "/ECSPI3_SS2") (class "Default")
      (node (ref "U800") (pin "B3") (pinfunction "IO_L4P_0_B3") (pintype "bidirectional"))
    )
    (net (code "36") (name "/EIM_A16") (class "Default")
      (node (ref "U800") (pin "A11") (pinfunction "IO_L39N_0_A11") (pintype "bidirectional"))
    )
    (net (code "37") (name "/EIM_A17") (class "Default")
      (node (ref "U800") (pin "B12") (pinfunction "IO_L41P_0_B12") (pintype "bidirectional"))
    )
    (net (code "38") (name "/EIM_A18") (class "Default")
      (node (ref "U800") (pin "D14") (pinfunction "IO_L65P_SCP3_0_D14") (pintype "bidirectional"))
    )
    (net (code "39") (name "/EIM_BCLK") (class "Default")
      (node (ref "U800") (pin "C9") (pinfunction "IO_L34N_GCLK18_0_C9") (pintype "bidirectional"))
    )
    (net (code "40") (name "/EIM_CS0") (class "Default")
      (node (ref "U800") (pin "B11") (pinfunction "IO_L39P_0_B11") (pintype "bidirectional"))
    )
    (net (code "41") (name "/EIM_CS1") (class "Default")
      (node (ref "U800") (pin "A15") (pinfunction "IO_L64N_SCP4_0_A15") (pintype "bidirectional"))
    )
    (net (code "42") (name "/EIM_DA0") (class "Default")
      (node (ref "U800") (pin "G9") (pinfunction "IO_L38P_0_G9") (pintype "bidirectional"))
    )
    (net (code "43") (name "/EIM_DA1") (class "Default")
      (node (ref "U800") (pin "A10") (pinfunction "IO_L37N_GCLK12_0_A10") (pintype "bidirectional"))
    )
    (net (code "44") (name "/EIM_DA2") (class "Default")
      (node (ref "U800") (pin "F9") (pinfunction "IO_L38N_VREF_0_F9") (pintype "bidirectional"))
    )
    (net (code "45") (name "/EIM_DA3") (class "Default")
      (node (ref "U800") (pin "B9") (pinfunction "IO_L35P_GCLK17_0_B9") (pintype "bidirectional"))
    )
    (net (code "46") (name "/EIM_DA4") (class "Default")
      (node (ref "U800") (pin "E13") (pinfunction "IO_L63N_SCP6_0_E13") (pintype "bidirectional"))
    )
    (net (code "47") (name "/EIM_DA5") (class "Default")
      (node (ref "U800") (pin "F13") (pinfunction "IO_L63P_SCP7_0_F13") (pintype "bidirectional"))
    )
    (net (code "48") (name "/EIM_DA6") (class "Default")
      (node (ref "U800") (pin "A9") (pinfunction "IO_L35N_GCLK16_0_A9") (pintype "bidirectional"))
    )
    (net (code "49") (name "/EIM_DA7") (class "Default")
      (node (ref "U800") (pin "A8") (pinfunction "IO_L33N_0_A8") (pintype "bidirectional"))
    )
    (net (code "50") (name "/EIM_DA8") (class "Default")
      (node (ref "U800") (pin "B8") (pinfunction "IO_L33P_0_B8") (pintype "bidirectional"))
    )
    (net (code "51") (name "/EIM_DA9") (class "Default")
      (node (ref "U800") (pin "D8") (pinfunction "IO_L11P_0_D8") (pintype "bidirectional"))
    )
    (net (code "52") (name "/EIM_DA10") (class "Default")
      (node (ref "U800") (pin "D11") (pinfunction "IO_L36P_GCLK15_0_D11") (pintype "bidirectional"))
    )
    (net (code "53") (name "/EIM_DA11") (class "Default")
      (node (ref "U800") (pin "C8") (pinfunction "IO_L11N_0_C8") (pintype "bidirectional"))
    )
    (net (code "54") (name "/EIM_DA12") (class "Default")
      (node (ref "U800") (pin "C7") (pinfunction "IO_L10P_0_C7") (pintype "bidirectional"))
    )
    (net (code "55") (name "/EIM_DA13") (class "Default")
      (node (ref "U800") (pin "C11") (pinfunction "IO_L36N_GCLK14_0_C11") (pintype "bidirectional"))
    )
    (net (code "56") (name "/EIM_DA14") (class "Default")
      (node (ref "U800") (pin "C4") (pinfunction "IO_L1N_VREF_0_C4") (pintype "bidirectional"))
    )
    (net (code "57") (name "/EIM_DA15") (class "Default")
      (node (ref "U800") (pin "B6") (pinfunction "IO_L8P_0_B6") (pintype "bidirectional"))
    )
    (net (code "58") (name "/EIM_LBA") (class "Default")
      (node (ref "U800") (pin "B14") (pinfunction "IO_L62P_0_B14") (pintype "bidirectional"))
    )
    (net (code "59") (name "/EIM_OE") (class "Default")
      (node (ref "U800") (pin "C10") (pinfunction "IO_L37P_GCLK13_0_C10") (pintype "bidirectional"))
    )
    (net (code "60") (name "/EIM_RW") (class "Default")
      (node (ref "U800") (pin "C14") (pinfunction "IO_L65N_SCP2_0_C14") (pintype "bidirectional"))
    )
    (net (code "61") (name "/EIM_WAIT") (class "Default")
      (node (ref "U800") (pin "A7") (pinfunction "IO_L10N_0_A7") (pintype "bidirectional"))
    )
    (net (code "62") (name "/EPIT1_EPITO") (class "Default")
      (node (ref "U800") (pin "H12") (pinfunction "IO_L32P_A17_M1A8_1_H12") (pintype "bidirectional"))
    )
    (net (code "63") (name "/FPGA_DONE") (class "Default")
      (node (ref "D10F") (pin "2") (pinfunction "K_2") (pintype "passive"))
      (node (ref "U800") (pin "V17") (pinfunction "DONE_2_V17") (pintype "bidirectional"))
    )
    (net (code "64") (name "/FPGA_HSWAPEN") (class "Default")
      (node (ref "R12F") (pin "2") (pinfunction "2_2") (pintype "passive"))
      (node (ref "R13F") (pin "1") (pinfunction "1_1") (pintype "passive"))
      (node (ref "U800") (pin "D4") (pinfunction "IO_L1P_HSWAPEN_0_D4") (pintype "bidirectional"))
    )
    (net (code "65") (name "/FPGA_INIT_N") (class "Default")
      (node (ref "R21F") (pin "2") (pinfunction "2_2") (pintype "passive"))
      (node (ref "U800") (pin "U3") (pinfunction "IO_L65P_INIT_B_2_U3") (pintype "bidirectional"))
    )
    (net (code "66") (name "/FPGA_LED2") (class "Default")
      (node (ref "D12F") (pin "1") (pinfunction "A_1") (pintype "passive"))
      (node (ref "U800") (pin "P18") (pinfunction "IO_L49N_M1DQ11_1_P18") (pintype "bidirectional"))
    )
    (net (code "67") (name "/FPGA_LI2C_SCL") (class "Default")
      (node (ref "R29F") (pin "2") (pinfunction "2_2") (pintype "passive"))
      (node (ref "U13F") (pin "6") (pinfunction "SCL_6") (pintype "input"))
      (node (ref "U800") (pin "E4") (pinfunction "IO_L54P_M3RESET_3_E4") (pintype "bidirectional"))
    )
    (net (code "68") (name "/FPGA_LI2C_SDA") (class "Default")
      (node (ref "R30F") (pin "2") (pinfunction "2_2") (pintype "passive"))
      (node (ref "U13F") (pin "5") (pinfunction "SDA_5") (pintype "bidirectional"))
      (node (ref "U800") (pin "E1") (pinfunction "IO_L50N_M3BA2_3_E1") (pintype "bidirectional"))
    )
    (net (code "69") (name "/FPGA_LI2C_WP") (class "Default")
      (node (ref "P_LI2C_WP") (pin "1") (pinfunction "1_1") (pintype "passive"))
      (node (ref "U13F") (pin "7") (pinfunction "WP_7") (pintype "input"))
      (node (ref "U800") (pin "G1") (pinfunction "IO_L46N_M3CLKN_3_G1") (pintype "bidirectional"))
    )
    (net (code "70") (name "/FPGA_LSPI_CLK") (class "Default")
      (node (ref "U14F") (pin "6") (pinfunction "CLK_6") (pintype "input"))
      (node (ref "U800") (pin "D3") (pinfunction "IO_L54N_M3A11_3_D3") (pintype "bidirectional"))
    )
    (net (code "71") (name "/FPGA_LSPI_CS") (class "Default")
      (node (ref "U14F") (pin "1") (pinfunction "~{CS}_1") (pintype "input"))
      (node (ref "U800") (pin "D1") (pinfunction "IO_L52N_M3A9_3_D1") (pintype "bidirectional"))
    )
    (net (code "72") (name "/FPGA_LSPI_HOLD") (class "Default")
      (node (ref "U14F") (pin "7") (pinfunction "~{HOLD}_7") (pintype "bidirectional"))
      (node (ref "U800") (pin "E3") (pinfunction "IO_L50P_M3WE_3_E3") (pintype "bidirectional"))
    )
    (net (code "73") (name "/FPGA_LSPI_MISO") (class "Default")
      (node (ref "U14F") (pin "2") (pinfunction "DO_2") (pintype "output"))
      (node (ref "U800") (pin "D2") (pinfunction "IO_L52P_M3A8_3_D2") (pintype "bidirectional"))
    )
    (net (code "74") (name "/FPGA_LSPI_MOSI") (class "Default")
      (node (ref "U14F") (pin "5") (pinfunction "DI_5") (pintype "input"))
      (node (ref "U800") (pin "C2") (pinfunction "IO_L83P_3_C2") (pintype "bidirectional"))
    )
    (net (code "75") (name "/FPGA_LSPI_WP") (class "Default")
      (node (ref "P_LSPI_WP") (pin "2") (pinfunction "2_2") (pintype "passive"))
      (node (ref "U14F") (pin "3") (pinfunction "~{WP}_3") (pintype "input"))
      (node (ref "U800") (pin "C1") (pinfunction "IO_L83N_VREF_3_C1") (pintype "bidirectional"))
    )
    (net (code "76") (name "/FPGA_M0") (class "Default")
      (node (ref "R14F") (pin "2") (pinfunction "2_2") (pintype "passive"))
      (node (ref "R15F") (pin "2") (pinfunction "2_2") (pintype "passive"))
      (node (ref "U800") (pin "T15") (pinfunction "IO_L1N_M0_CMPMISO_2_T15") (pintype "bidirectional"))
    )
    (net (code "77") (name "/FPGA_M1") (class "Default")
      (node (ref "R16F") (pin "2") (pinfunction "2_2") (pintype "passive"))
      (node (ref "R17F") (pin "2") (pinfunction "2_2") (pintype "passive"))
      (node (ref "U800") (pin "N12") (pinfunction "IO_L13P_M1_2_N12") (pintype "bidirectional"))
    )
    (net (code "78") (name "/FPGA_PWM0") (class "Default")
      (node (ref "D19F") (pin "1") (pinfunction "IO1A_1") (pintype "bidirectional"))
      (node (ref "D19F") (pin "10") (pinfunction "IO1B_10") (pintype "bidirectional"))
      (node (ref "RP12F") (pin "5") (pinfunction "R42_5") (pintype "passive"))
      (node (ref "U800") (pin "C18") (pinfunction "IO_L29N_A22_M1A14_1_C18") (pintype "bidirectional"))
    )
    (net (code "79") (name "/FPGA_PWM1") (class "Default")
      (node (ref "D19F") (pin "2") (pinfunction "IO2A_2") (pintype "bidirectional"))
      (node (ref "D19F") (pin "9") (pinfunction "IO2B_9") (pintype "bidirectional"))
      (node (ref "RP12F") (pin "6") (pinfunction "R32_6") (pintype "passive"))
      (node (ref "U800") (pin "C17") (pinfunction "IO_L29P_A23_M1A13_1_C17") (pintype "bidirectional"))
    )
    (net (code "80") (name "/FPGA_PWM2") (class "Default")
      (node (ref "D19F") (pin "4") (pinfunction "IO3A_4") (pintype "bidirectional"))
      (node (ref "D19F") (pin "7") (pinfunction "IO3B_7") (pintype "bidirectional"))
      (node (ref "RP12F") (pin "7") (pinfunction "R22_7") (pintype "passive"))
      (node (ref "U800") (pin "D17") (pinfunction "IO_L31P_A19_M1CKE_1_D17") (pintype "bidirectional"))
    )
    (net (code "81") (name "/FPGA_PWM3") (class "Default")
      (node (ref "D19F") (pin "5") (pinfunction "IO4A_5") (pintype "bidirectional"))
      (node (ref "D19F") (pin "6") (pinfunction "IO4B_6") (pintype "bidirectional"))
      (node (ref "RP12F") (pin "8") (pinfunction "R12_8") (pintype "passive"))
      (node (ref "U800") (pin "D18") (pinfunction "IO_L31N_A18_M1A12_1_D18") (pintype "bidirectional"))
    )
    (net (code "82") (name "/FPGA_PWM4") (class "Default")
      (node (ref "D15F") (pin "1") (pinfunction "IO1A_1") (pintype "bidirectional"))
      (node (ref "D15F") (pin "10") (pinfunction "IO1B_10") (pintype "bidirectional"))
      (node (ref "RP15F") (pin "5") (pinfunction "R42_5") (pintype "passive"))
      (node (ref "U800") (pin "E18") (pinfunction "IO_L33N_A14_M1A4_1_E18") (pintype "bidirectional"))
    )
    (net (code "83") (name "/FPGA_PWM5") (class "Default")
      (node (ref "D15F") (pin "2") (pinfunction "IO2A_2") (pintype "bidirectional"))
      (node (ref "D15F") (pin "9") (pinfunction "IO2B_9") (pintype "bidirectional"))
      (node (ref "RP15F") (pin "6") (pinfunction "R32_6") (pintype "passive"))
      (node (ref "U800") (pin "E16") (pinfunction "IO_L33P_A15_M1A10_1_E16") (pintype "bidirectional"))
    )
    (net (code "84") (name "/FPGA_PWM6") (class "Default")
      (node (ref "D15F") (pin "4") (pinfunction "IO3A_4") (pintype "bidirectional"))
      (node (ref "D15F") (pin "7") (pinfunction "IO3B_7") (pintype "bidirectional"))
      (node (ref "RP15F") (pin "7") (pinfunction "R22_7") (pintype "passive"))
      (node (ref "U800") (pin "F17") (pinfunction "IO_L35P_A11_M1A7_1_F17") (pintype "bidirectional"))
    )
    (net (code "85") (name "/FPGA_PWM7") (class "Default")
      (node (ref "D15F") (pin "5") (pinfunction "IO4A_5") (pintype "bidirectional"))
      (node (ref "D15F") (pin "6") (pinfunction "IO4B_6") (pintype "bidirectional"))
      (node (ref "RP15F") (pin "8") (pinfunction "R12_8") (pintype "passive"))
      (node (ref "U800") (pin "F18") (pinfunction "IO_L35N_A10_M1A2_1_F18") (pintype "bidirectional"))
    )
    (net (code "86") (name "/FPGA_RESET_N") (class "Default")
      (node (ref "R25F") (pin "1") (pinfunction "1_1") (pintype "passive"))
      (node (ref "U11F") (pin "6") (pinfunction "C_6") (pintype "input"))
      (node (ref "U800") (pin "V2") (pinfunction "PROGRAM_B_2_V2") (pintype "input"))
    )
    (net (code "87") (name "/FPGA_SUSPEND") (class "Default")
      (node (ref "R23F") (pin "2") (pinfunction "2_2") (pintype "passive"))
      (node (ref "U800") (pin "R16") (pinfunction "SUSPEND_R16") (pintype "input"))
    )
    (net (code "88") (name "/FPGA_TCK") (class "Default")
      (node (ref "P10F") (pin "2") (pinfunction "2_2") (pintype "passive"))
      (node (ref "U800") (pin "A17") (pinfunction "TCK_A17") (pintype "input"))
    )
    (net (code "89") (name "/FPGA_TDI") (class "Default")
      (node (ref "P10F") (pin "3") (pinfunction "3_3") (pintype "passive"))
      (node (ref "U800") (pin "D15") (pinfunction "TDI_D15") (pintype "input"))
    )
    (net (code "90") (name "/FPGA_TDO") (class "Default")
      (node (ref "P10F") (pin "4") (pinfunction "4_4") (pintype "passive"))
      (node (ref "U800") (pin "D16") (pinfunction "TDO_D16") (pintype "output"))
    )
    (net (code "91") (name "/FPGA_TMS") (class "Default")
      (node (ref "P10F") (pin "5") (pinfunction "5_5") (pintype "passive"))
      (node (ref "U800") (pin "B18") (pinfunction "TMS_B18") (pintype "input"))
    )
    (net (code "92") (name "/F_ADC0_CS") (class "Default")
      (node (ref "R28F") (pin "2") (pinfunction "2_2") (pintype "passive"))
      (node (ref "U12F") (pin "1") (pinfunction "~{CS}_1") (pintype "input"))
      (node (ref "U800") (pin "K17") (pinfunction "IO_L45P_A1_M1LDQS_1_K17") (pintype "bidirectional"))
    )
    (net (code "93") (name "/F_ADC_IN") (class "Default")
      (node (ref "U12F") (pin "14") (pinfunction "DIN_14") (pintype "input"))
      (node (ref "U800") (pin "P17") (pinfunction "IO_L49P_M1DQ10_1_P17") (pintype "bidirectional"))
    )
    (net (code "94") (name "/F_ADC_OUT") (class "Default")
      (node (ref "U12F") (pin "15") (pinfunction "DOUT_15") (pintype "output"))
      (node (ref "U800") (pin "N17") (pinfunction "IO_L48P_HDC_M1DQ8_1_N17") (pintype "bidirectional"))
    )
    (net (code "95") (name "/F_ADC_SCLK") (class "Default")
      (node (ref "U12F") (pin "16") (pinfunction "SCLK_16") (pintype "input"))
      (node (ref "U800") (pin "N18") (pinfunction "IO_L48N_M1DQ9_1_N18") (pintype "bidirectional"))
    )
    (net (code "96") (name "/F_DIGIO0") (class "Default")
      (node (ref "D17F") (pin "1") (pinfunction "IO1A_1") (pintype "bidirectional"))
      (node (ref "D17F") (pin "10") (pinfunction "IO1B_10") (pintype "bidirectional"))
      (node (ref "RP11F") (pin "4") (pinfunction "R4_4") (pintype "passive"))
      (node (ref "U800") (pin "H18") (pinfunction "IO_L43N_GCLK4_M1DQ5_1_H18") (pintype "bidirectional"))
    )
    (net (code "97") (name "/F_DIGIO1") (class "Default")
      (node (ref "D17F") (pin "2") (pinfunction "IO2A_2") (pintype "bidirectional"))
      (node (ref "D17F") (pin "9") (pinfunction "IO2B_9") (pintype "bidirectional"))
      (node (ref "RP11F") (pin "3") (pinfunction "R3_3") (pintype "passive"))
      (node (ref "U800") (pin "G18") (pinfunction "IO_L38N_A4_M1CLKN_1_G18") (pintype "bidirectional"))
    )
    (net (code "98") (name "/F_DIGIO2") (class "Default")
      (node (ref "D17F") (pin "4") (pinfunction "IO3A_4") (pintype "bidirectional"))
      (node (ref "D17F") (pin "7") (pinfunction "IO3B_7") (pintype "bidirectional"))
      (node (ref "RP11F") (pin "2") (pinfunction "R2_2") (pintype "passive"))
      (node (ref "U800") (pin "H17") (pinfunction "IO_L43P_GCLK5_M1DQ4_1_H17") (pintype "bidirectional"))
    )
    (net (code "99") (name "/F_DIGIO3") (class "Default")
      (node (ref "D17F") (pin "5") (pinfunction "IO4A_5") (pintype "bidirectional"))
      (node (ref "D17F") (pin "6") (pinfunction "IO4B_6") (pintype "bidirectional"))
      (node (ref "RP11F") (pin "1") (pinfunction "R1_1") (pintype "passive"))
      (node (ref "U800") (pin "H16") (pinfunction "IO_L37N_A6_M1A1_1_H16") (pintype "bidirectional"))
    )
    (net (code "100") (name "/F_DIGIO4") (class "Default")
      (node (ref "D14F") (pin "1") (pinfunction "IO1A_1") (pintype "bidirectional"))
      (node (ref "D14F") (pin "10") (pinfunction "IO1B_10") (pintype "bidirectional"))
      (node (ref "RP14F") (pin "4") (pinfunction "R4_4") (pintype "passive"))
      (node (ref "U800") (pin "G16") (pinfunction "IO_L38P_A5_M1CLK_1_G16") (pintype "bidirectional"))
    )
    (net (code "101") (name "/F_DIGIO5") (class "Default")
      (node (ref "D14F") (pin "2") (pinfunction "IO2A_2") (pintype "bidirectional"))
      (node (ref "D14F") (pin "9") (pinfunction "IO2B_9") (pintype "bidirectional"))
      (node (ref "RP14F") (pin "3") (pinfunction "R3_3") (pintype "passive"))
      (node (ref "U800") (pin "F16") (pinfunction "IO_L1N_A24_VREF_1_F16") (pintype "bidirectional"))
    )
    (net (code "102") (name "/F_DIGIO6") (class "Default")
      (node (ref "D14F") (pin "4") (pinfunction "IO3A_4") (pintype "bidirectional"))
      (node (ref "D14F") (pin "7") (pinfunction "IO3B_7") (pintype "bidirectional"))
      (node (ref "RP14F") (pin "2") (pinfunction "R2_2") (pintype "passive"))
      (node (ref "U800") (pin "G14") (pinfunction "IO_L30N_A20_M1A11_1_G14") (pintype "bidirectional"))
    )
    (net (code "103") (name "/F_DIGIO7") (class "Default")
      (node (ref "D14F") (pin "5") (pinfunction "IO4A_5") (pintype "bidirectional"))
      (node (ref "D14F") (pin "6") (pinfunction "IO4B_6") (pintype "bidirectional"))
      (node (ref "RP14F") (pin "1") (pinfunction "R1_1") (pintype "passive"))
      (node (ref "U800") (pin "F14") (pinfunction "IO_L30P_A21_M1RESET_1_F14") (pintype "bidirectional"))
    )
    (net (code "104") (name "/F_DIGIO_X0") (class "Default")
      (node (ref "P13F") (pin "1") (pinfunction "1_1") (pintype "passive"))
      (node (ref "RP11F") (pin "5") (pinfunction "R42_5") (pintype "passive"))
    )
    (net (code "105") (name "/F_DIGIO_X1") (class "Default")
      (node (ref "P13F") (pin "2") (pinfunction "2_2") (pintype "passive"))
      (node (ref "RP11F") (pin "6") (pinfunction "R32_6") (pintype "passive"))
    )
    (net (code "106") (name "/F_DIGIO_X2") (class "Default")
      (node (ref "P13F") (pin "3") (pinfunction "3_3") (pintype "passive"))
      (node (ref "RP11F") (pin "7") (pinfunction "R22_7") (pintype "passive"))
    )
    (net (code "107") (name "/F_DIGIO_X3") (class "Default")
      (node (ref "P13F") (pin "4") (pinfunction "4_4") (pintype "passive"))
      (node (ref "RP11F") (pin "8") (pinfunction "R12_8") (pintype "passive"))
    )
    (net (code "108") (name "/F_DIGIO_X4") (class "Default")
      (node (ref "P13F") (pin "5") (pinfunction "5_5") (pintype "passive"))
      (node (ref "RP14F") (pin "5") (pinfunction "R42_5") (pintype "passive"))
    )
    (net (code "109") (name "/F_DIGIO_X5") (class "Default")
      (node (ref "P13F") (pin "6") (pinfunction "6_6") (pintype "passive"))
      (node (ref "RP14F") (pin "6") (pinfunction "R32_6") (pintype "passive"))
    )
    (net (code "110") (name "/F_DIGIO_X6") (class "Default")
      (node (ref "P13F") (pin "7") (pinfunction "7_7") (pintype "passive"))
      (node (ref "RP14F") (pin "7") (pinfunction "R22_7") (pintype "passive"))
    )
    (net (code "111") (name "/F_DIGIO_X7") (class "Default")
      (node (ref "P13F") (pin "8") (pinfunction "8_8") (pintype "passive"))
      (node (ref "RP14F") (pin "8") (pinfunction "R12_8") (pintype "passive"))
    )
    (net (code "112") (name "/F_PWM0") (class "Default")
      (node (ref "P15F") (pin "1") (pinfunction "1_1") (pintype "passive"))
      (node (ref "RP12F") (pin "4") (pinfunction "R4_4") (pintype "passive"))
    )
    (net (code "113") (name "/F_PWM1") (class "Default")
      (node (ref "P15F") (pin "3") (pinfunction "3_3") (pintype "passive"))
      (node (ref "RP12F") (pin "3") (pinfunction "R3_3") (pintype "passive"))
    )
    (net (code "114") (name "/F_PWM2") (class "Default")
      (node (ref "P15F") (pin "5") (pinfunction "5_5") (pintype "passive"))
      (node (ref "RP12F") (pin "2") (pinfunction "R2_2") (pintype "passive"))
    )
    (net (code "115") (name "/F_PWM3") (class "Default")
      (node (ref "P15F") (pin "7") (pinfunction "7_7") (pintype "passive"))
      (node (ref "RP12F") (pin "1") (pinfunction "R1_1") (pintype "passive"))
    )
    (net (code "116") (name "/F_PWM4") (class "Default")
      (node (ref "P15F") (pin "9") (pinfunction "9_9") (pintype "passive"))
      (node (ref "RP15F") (pin "4") (pinfunction "R4_4") (pintype "passive"))
    )
    (net (code "117") (name "/F_PWM5") (class "Default")
      (node (ref "P15F") (pin "11") (pinfunction "11_11") (pintype "passive"))
      (node (ref "RP15F") (pin "3") (pinfunction "R3_3") (pintype "passive"))
    )
    (net (code "118") (name "/F_PWM6") (class "Default")
      (node (ref "P15F") (pin "13") (pinfunction "13_13") (pintype "passive"))
      (node (ref "RP15F") (pin "2") (pinfunction "R2_2") (pintype "passive"))
    )
    (net (code "119") (name "/F_PWM7") (class "Default")
      (node (ref "P15F") (pin "15") (pinfunction "15_15") (pintype "passive"))
      (node (ref "RP15F") (pin "1") (pinfunction "R1_1") (pintype "passive"))
    )
    (net (code "120") (name "/I2C3_SCL") (class "Default")
      (node (ref "U800") (pin "P4") (pinfunction "IO_L2P_3_P4") (pintype "bidirectional"))
    )
    (net (code "121") (name "/I2C3_SDA") (class "Default")
      (node (ref "U800") (pin "P3") (pinfunction "IO_L2N_3_P3") (pintype "bidirectional"))
    )
    (net (code "122") (name "/RESETBMCU") (class "Default")
      (node (ref "Q10F") (pin "3") (pinfunction "D_3") (pintype "passive"))
      (node (ref "U800") (pin "K18") (pinfunction "IO_L45N_A0_M1LDQSN_1_K18") (pintype "bidirectional"))
    )
    (net (code "123") (name "/SMB_SCL") (class "Default")
      (node (ref "U800") (pin "N3") (pinfunction "IO_L1N_VREF_3_N3") (pintype "bidirectional"))
    )
    (net (code "124") (name "/SMB_SDA") (class "Default")
      (node (ref "U800") (pin "N4") (pinfunction "IO_L1P_3_N4") (pintype "bidirectional"))
    )
    (net (code "125") (name "/UART3_RXD") (class "Default")
      (node (ref "U800") (pin "P2") (pinfunction "IO_L34P_M3UDQS_3_P2") (pintype "bidirectional"))
    )
    (net (code "126") (name "/UART3_TXD") (class "Default")
      (node (ref "U800") (pin "T2") (pinfunction "IO_L33P_M3DQ12_3_T2") (pintype "bidirectional"))
    )
    (net (code "127") (name "/UART4_CTS") (class "Default")
      (node (ref "U800") (pin "U1") (pinfunction "IO_L32N_M3DQ15_3_U1") (pintype "bidirectional"))
    )
    (net (code "128") (name "/UART4_RTS") (class "Default")
      (node (ref "U800") (pin "U2") (pinfunction "IO_L32P_M3DQ14_3_U2") (pintype "bidirectional"))
    )
    (net (code "129") (name "/UART4_RXD") (class "Default")
      (node (ref "U800") (pin "T1") (pinfunction "IO_L33N_M3DQ13_3_T1") (pintype "bidirectional"))
    )
    (net (code "130") (name "/UART4_TXD") (class "Default")
      (node (ref "U800") (pin "P1") (pinfunction "IO_L34N_M3UDQSN_3_P1") (pintype "bidirectional"))
    )
    (net (code "131") (name "/UIM_CLK") (class "Default")
      (node (ref "U800") (pin "B16") (pinfunction "IO_L66P_SCP1_0_B16") (pintype "bidirectional"))
    )
    (net (code "132") (name "/UIM_DATA") (class "Default")
      (node (ref "U800") (pin "A12") (pinfunction "IO_L41N_0_A12") (pintype "bidirectional"))
    )
    (net (code "133") (name "/UIM_PWR") (class "Default")
      (node (ref "U800") (pin "J18") (pinfunction "IO_L44N_A2_M1DQ7_1_J18") (pintype "bidirectional"))
    )
    (net (code "134") (name "/UIM_PWRON") (class "Default")
      (node (ref "U800") (pin "A14") (pinfunction "IO_L62N_VREF_0_A14") (pintype "bidirectional"))
    )
    (net (code "135") (name "/UIM_RESET") (class "Default")
      (node (ref "U800") (pin "C15") (pinfunction "IO_L64P_SCP5_0_C15") (pintype "bidirectional"))
    )
    (net (code "136") (name "/WDOG_RST_B") (class "Default")
      (node (ref "U800") (pin "U16") (pinfunction "IO_L2P_CMPCLK_2_U16") (pintype "bidirectional"))
    )
    (net (code "137") (name "GND") (class "Default")
      (node (ref "C10F") (pin "2") (pinfunction "2_2") (pintype "passive"))
      (node (ref "C11F") (pin "2") (pinfunction "2_2") (pintype "passive"))
      (node (ref "C12F") (pin "2") (pinfunction "2_2") (pintype "passive"))
      (node (ref "C13F") (pin "2") (pinfunction "2_2") (pintype "passive"))
      (node (ref "C14F") (pin "2") (pinfunction "2_2") (pintype "passive"))
      (node (ref "C15F") (pin "2") (pinfunction "2_2") (pintype "passive"))
      (node (ref "C16F") (pin "2") (pinfunction "2_2") (pintype "passive"))
      (node (ref "C17F") (pin "2") (pinfunction "2_2") (pintype "passive"))
      (node (ref "C18F") (pin "2") (pinfunction "2_2") (pintype "passive"))
      (node (ref "C19F") (pin "2") (pinfunction "2_2") (pintype "passive"))
      (node (ref "C20F") (pin "1") (pinfunction "1_1") (pintype "passive"))
      (node (ref "C21F") (pin "2") (pinfunction "2_2") (pintype "passive"))
      (node (ref "C22F") (pin "2") (pinfunction "2_2") (pintype "passive"))
      (node (ref "C23F") (pin "2") (pinfunction "2_2") (pintype "passive"))
      (node (ref "C24F") (pin "2") (pinfunction "2_2") (pintype "passive"))
      (node (ref "C25F") (pin "2") (pinfunction "2_2") (pintype "passive"))
      (node (ref "C26F") (pin "2") (pinfunction "2_2") (pintype "passive"))
      (node (ref "C27F") (pin "2") (pinfunction "2_2") (pintype "passive"))
      (node (ref "C28F") (pin "2") (pinfunction "2_2") (pintype "passive"))
      (node (ref "C29F") (pin "2") (pinfunction "2_2") (pintype "passive"))
      (node (ref "C30F") (pin "1") (pinfunction "1_1") (pintype "passive"))
      (node (ref "C31F") (pin "2") (pinfunction "2_2") (pintype "passive"))
      (node (ref "C32F") (pin "2") (pinfunction "2_2") (pintype "passive"))
      (node (ref "C33F") (pin "2") (pinfunction "2_2") (pintype "passive"))
      (node (ref "C34F") (pin "2") (pinfunction "2_2") (pintype "passive"))
      (node (ref "C35F") (pin "2") (pinfunction "2_2") (pintype "passive"))
      (node (ref "C36F") (pin "2") (pinfunction "2_2") (pintype "passive"))
      (node (ref "C37F") (pin "2") (pinfunction "2_2") (pintype "passive"))
      (node (ref "C38F") (pin "2") (pinfunction "2_2") (pintype "passive"))
      (node (ref "C39F") (pin "2") (pinfunction "2_2") (pintype "passive"))
      (node (ref "C40F") (pin "1") (pinfunction "1_1") (pintype "passive"))
      (node (ref "C41F") (pin "2") (pinfunction "2_2") (pintype "passive"))
      (node (ref "C42F") (pin "2") (pinfunction "2_2") (pintype "passive"))
      (node (ref "C43F") (pin "2") (pinfunction "2_2") (pintype "passive"))
      (node (ref "C44F") (pin "2") (pinfunction "2_2") (pintype "passive"))
      (node (ref "C45F") (pin "2") (pinfunction "2_2") (pintype "passive"))
      (node (ref "C46F") (pin "2") (pinfunction "2_2") (pintype "passive"))
      (node (ref "C47F") (pin "2") (pinfunction "2_2") (pintype "passive"))
      (node (ref "C48F") (pin "2") (pinfunction "2_2") (pintype "passive"))
      (node (ref "C49F") (pin "1") (pinfunction "1_1") (pintype "passive"))
      (node (ref "C50F") (pin "2") (pinfunction "2_2") (pintype "passive"))
      (node (ref "C51F") (pin "2") (pinfunction "2_2") (pintype "passive"))
      (node (ref "C52F") (pin "2") (pinfunction "2_2") (pintype "passive"))
      (node (ref "C53F") (pin "2") (pinfunction "2_2") (pintype "passive"))
      (node (ref "C54F") (pin "2") (pinfunction "2_2") (pintype "passive"))
      (node (ref "C55F") (pin "2") (pinfunction "2_2") (pintype "passive"))
      (node (ref "C56F") (pin "2") (pinfunction "2_2") (pintype "passive"))
      (node (ref "C57F") (pin "2") (pinfunction "2_2") (pintype "passive"))
      (node (ref "C58F") (pin "2") (pinfunction "2_2") (pintype "passive"))
      (node (ref "C59F") (pin "2") (pinfunction "2_2") (pintype "passive"))
      (node (ref "C60F") (pin "1") (pinfunction "1_1") (pintype "passive"))
      (node (ref "C61F") (pin "2") (pinfunction "2_2") (pintype "passive"))
      (node (ref "C62F") (pin "1") (pinfunction "1_1") (pintype "passive"))
      (node (ref "C63F") (pin "1") (pinfunction "1_1") (pintype "passive"))
      (node (ref "C64F") (pin "2") (pinfunction "2_2") (pintype "passive"))
      (node (ref "C65F") (pin "2") (pinfunction "2_2") (pintype "passive"))
      (node (ref "C66F") (pin "2") (pinfunction "2_2") (pintype "passive"))
      (node (ref "C67F") (pin "2") (pinfunction "2_2") (pintype "passive"))
      (node (ref "C68F") (pin "2") (pinfunction "2_2") (pintype "passive"))
      (node (ref "C69F") (pin "2") (pinfunction "2_2") (pintype "passive"))
      (node (ref "C70F") (pin "2") (pinfunction "2_2") (pintype "passive"))
      (node (ref "C71F") (pin "2") (pinfunction "2_2") (pintype "passive"))
      (node (ref "C72F") (pin "1") (pinfunction "1_1") (pintype "passive"))
      (node (ref "C73F") (pin "1") (pinfunction "1_1") (pintype "passive"))
      (node (ref "C74F") (pin "1") (pinfunction "1_1") (pintype "passive"))
      (node (ref "C75F") (pin "2") (pinfunction "2_2") (pintype "passive"))
      (node (ref "D11F") (pin "1") (pinfunction "A_1") (pintype "passive"))
      (node (ref "D13F") (pin "3") (pinfunction "GND1_3") (pintype "input"))
      (node (ref "D14F") (pin "3") (pinfunction "GND1_3") (pintype "input"))
      (node (ref "D15F") (pin "3") (pinfunction "GND1_3") (pintype "input"))
      (node (ref "D16F") (pin "3") (pinfunction "GND1_3") (pintype "input"))
      (node (ref "D17F") (pin "3") (pinfunction "GND1_3") (pintype "input"))
      (node (ref "D18F") (pin "2") (pinfunction "A_2") (pintype "passive"))
      (node (ref "D19F") (pin "3") (pinfunction "GND1_3") (pintype "input"))
      (node (ref "D20F") (pin "2") (pinfunction "A_2") (pintype "passive"))
      (node (ref "D21F") (pin "2") (pinfunction "A_2") (pintype "passive"))
      (node (ref "P10F") (pin "6") (pinfunction "6_6") (pintype "passive"))
      (node (ref "P12F") (pin "10") (pinfunction "10_10") (pintype "passive"))
      (node (ref "P12F") (pin "12") (pinfunction "12_12") (pintype "passive"))
      (node (ref "P12F") (pin "14") (pinfunction "14_14") (pintype "passive"))
      (node (ref "P12F") (pin "16") (pinfunction "16_16") (pintype "passive"))
      (node (ref "P12F") (pin "2") (pinfunction "2_2") (pintype "passive"))
      (node (ref "P12F") (pin "4") (pinfunction "4_4") (pintype "passive"))
      (node (ref "P12F") (pin "6") (pinfunction "6_6") (pintype "passive"))
      (node (ref "P12F") (pin "8") (pinfunction "8_8") (pintype "passive"))
      (node (ref "P14F") (pin "10") (pinfunction "10_10") (pintype "passive"))
      (node (ref "P14F") (pin "12") (pinfunction "12_12") (pintype "passive"))
      (node (ref "P14F") (pin "14") (pinfunction "14_14") (pintype "passive"))
      (node (ref "P14F") (pin "16") (pinfunction "16_16") (pintype "passive"))
      (node (ref "P14F") (pin "2") (pinfunction "2_2") (pintype "passive"))
      (node (ref "P14F") (pin "4") (pinfunction "4_4") (pintype "passive"))
      (node (ref "P14F") (pin "6") (pinfunction "6_6") (pintype "passive"))
      (node (ref "P14F") (pin "8") (pinfunction "8_8") (pintype "passive"))
      (node (ref "P16F") (pin "1") (pinfunction "1_1") (pintype "passive"))
      (node (ref "P16F") (pin "2") (pinfunction "2_2") (pintype "passive"))
      (node (ref "P16F") (pin "3") (pinfunction "3_3") (pintype "passive"))
      (node (ref "P16F") (pin "4") (pinfunction "4_4") (pintype "passive"))
      (node (ref "P16F") (pin "5") (pinfunction "5_5") (pintype "passive"))
      (node (ref "P16F") (pin "6") (pinfunction "6_6") (pintype "passive"))
      (node (ref "P16F") (pin "7") (pinfunction "7_7") (pintype "passive"))
      (node (ref "P16F") (pin "8") (pinfunction "8_8") (pintype "passive"))
      (node (ref "P_LSPI_WP") (pin "1") (pinfunction "1_1") (pintype "passive"))
      (node (ref "Q10F") (pin "2") (pinfunction "S_2") (pintype "passive"))
      (node (ref "R10F") (pin "1") (pinfunction "1_1") (pintype "passive"))
      (node (ref "R12F") (pin "1") (pinfunction "1_1") (pintype "passive"))
      (node (ref "R15F") (pin "1") (pinfunction "1_1") (pintype "passive"))
      (node (ref "R17F") (pin "1") (pinfunction "1_1") (pintype "passive"))
      (node (ref "R18F") (pin "2") (pinfunction "2_2") (pintype "passive"))
      (node (ref "R23F") (pin "1") (pinfunction "1_1") (pintype "passive"))
      (node (ref "R24F") (pin "2") (pinfunction "2_2") (pintype "passive"))
      (node (ref "R27F") (pin "1") (pinfunction "1_1") (pintype "passive"))
      (node (ref "U10F") (pin "2") (pinfunction "GND_2") (pintype "power_in"))
      (node (ref "U10F") (pin "7") (pinfunction "GND_7") (pintype "power_in"))
      (node (ref "U11F") (pin "2") (pinfunction "GND_2") (pintype "power_in"))
      (node (ref "U11F") (pin "3") (pinfunction "A_3") (pintype "input"))
      (node (ref "U12F") (pin "12") (pinfunction "DGND_12") (pintype "power_in"))
      (node (ref "U12F") (pin "3") (pinfunction "AGND_3") (pintype "power_in"))
      (node (ref "U13F") (pin "1") (pinfunction "A0_1") (pintype "input"))
      (node (ref "U13F") (pin "2") (pinfunction "A1_2") (pintype "input"))
      (node (ref "U13F") (pin "3") (pinfunction "A2_3") (pintype "input"))
      (node (ref "U13F") (pin "4") (pinfunction "GND_4") (pintype "power_in"))
      (node (ref "U14F") (pin "4") (pinfunction "VSS_4") (pintype "power_in"))
      (node (ref "U15F") (pin "2") (pinfunction "GND_2") (pintype "power_in"))
      (node (ref "U800") (pin "A1") (pinfunction "GND_A1") (pintype "power_in"))
      (node (ref "U800") (pin "A18") (pinfunction "GND_A18") (pintype "power_in"))
      (node (ref "U800") (pin "B13") (pinfunction "GND_B13") (pintype "power_in"))
      (node (ref "U800") (pin "B7") (pinfunction "GND_B7") (pintype "power_in"))
      (node (ref "U800") (pin "C16") (pinfunction "GND_C16") (pintype "power_in"))
      (node (ref "U800") (pin "C3") (pinfunction "GND_C3") (pintype "power_in"))
      (node (ref "U800") (pin "D10") (pinfunction "GND_D10") (pintype "power_in"))
      (node (ref "U800") (pin "D5") (pinfunction "GND_D5") (pintype "power_in"))
      (node (ref "U800") (pin "E15") (pinfunction "GND_E15") (pintype "power_in"))
      (node (ref "U800") (pin "G12") (pinfunction "GND_G12") (pintype "power_in"))
      (node (ref "U800") (pin "G17") (pinfunction "GND_G17") (pintype "power_in"))
      (node (ref "U800") (pin "G2") (pinfunction "GND_G2") (pintype "power_in"))
      (node (ref "U800") (pin "G5") (pinfunction "GND_G5") (pintype "power_in"))
      (node (ref "U800") (pin "H10") (pinfunction "GND_H10") (pintype "power_in"))
      (node (ref "U800") (pin "H8") (pinfunction "GND_H8") (pintype "power_in"))
      (node (ref "U800") (pin "J11") (pinfunction "GND_J11") (pintype "power_in"))
      (node (ref "U800") (pin "J15") (pinfunction "GND_J15") (pintype "power_in"))
      (node (ref "U800") (pin "J4") (pinfunction "GND_J4") (pintype "power_in"))
      (node (ref "U800") (pin "J9") (pinfunction "GND_J9") (pintype "power_in"))
      (node (ref "U800") (pin "K10") (pinfunction "GND_K10") (pintype "power_in"))
      (node (ref "U800") (pin "K8") (pinfunction "GND_K8") (pintype "power_in"))
      (node (ref "U800") (pin "L11") (pinfunction "GND_L11") (pintype "power_in"))
      (node (ref "U800") (pin "L9") (pinfunction "GND_L9") (pintype "power_in"))
      (node (ref "U800") (pin "M17") (pinfunction "GND_M17") (pintype "power_in"))
      (node (ref "U800") (pin "M2") (pinfunction "GND_M2") (pintype "power_in"))
      (node (ref "U800") (pin "M6") (pinfunction "GND_M6") (pintype "power_in"))
      (node (ref "U800") (pin "N13") (pinfunction "GND_N13") (pintype "power_in"))
      (node (ref "U800") (pin "R1") (pinfunction "GND_R1") (pintype "power_in"))
      (node (ref "U800") (pin "R14") (pinfunction "GND_R14") (pintype "power_in"))
      (node (ref "U800") (pin "R18") (pinfunction "GND_R18") (pintype "power_in"))
      (node (ref "U800") (pin "R4") (pinfunction "GND_R4") (pintype "power_in"))
      (node (ref "U800") (pin "R9") (pinfunction "GND_R9") (pintype "power_in"))
      (node (ref "U800") (pin "T16") (pinfunction "GND_T16") (pintype "power_in"))
      (node (ref "U800") (pin "U12") (pinfunction "GND_U12") (pintype "power_in"))
      (node (ref "U800") (pin "U6") (pinfunction "GND_U6") (pintype "power_in"))
      (node (ref "U800") (pin "V1") (pinfunction "GND_V1") (pintype "power_in"))
      (node (ref "U800") (pin "V18") (pinfunction "GND_V18") (pintype "power_in"))
    )
    (net (code "138") (name "Net-(D10F-A)") (class "Default")
      (node (ref "D10F") (pin "1") (pinfunction "A_1") (pintype "passive"))
      (node (ref "R22F") (pin "1") (pinfunction "1_1") (pintype "passive"))
    )
    (net (code "139") (name "Net-(D11F-K)") (class "Default")
      (node (ref "D11F") (pin "2") (pinfunction "K_2") (pintype "passive"))
      (node (ref "L10F") (pin "1") (pinfunction "1_1") (pintype "passive"))
      (node (ref "U10F") (pin "3") (pinfunction "SW_3") (pintype "passive"))
    )
    (net (code "140") (name "Net-(D12F-K)") (class "Default")
      (node (ref "D12F") (pin "2") (pinfunction "K_2") (pintype "passive"))
      (node (ref "R27F") (pin "2") (pinfunction "2_2") (pintype "passive"))
    )
    (net (code "141") (name "Net-(D21F-K)") (class "Default")
      (node (ref "C74F") (pin "2") (pinfunction "2_2") (pintype "passive"))
      (node (ref "D21F") (pin "1") (pinfunction "K_1") (pintype "passive"))
      (node (ref "P15F") (pin "10") (pinfunction "10_10") (pintype "passive"))
      (node (ref "P15F") (pin "12") (pinfunction "12_12") (pintype "passive"))
      (node (ref "P15F") (pin "14") (pinfunction "14_14") (pintype "passive"))
      (node (ref "P15F") (pin "16") (pinfunction "16_16") (pintype "passive"))
      (node (ref "P15F") (pin "2") (pinfunction "2_2") (pintype "passive"))
      (node (ref "P15F") (pin "4") (pinfunction "4_4") (pintype "passive"))
      (node (ref "P15F") (pin "6") (pinfunction "6_6") (pintype "passive"))
      (node (ref "P15F") (pin "8") (pinfunction "8_8") (pintype "passive"))
      (node (ref "P_PWM") (pin "1") (pinfunction "1_1") (pintype "passive"))
    )
    (net (code "142") (name "Net-(Q10F-G)") (class "Default")
      (node (ref "Q10F") (pin "1") (pinfunction "G_1") (pintype "passive"))
      (node (ref "R26F") (pin "1") (pinfunction "1_1") (pintype "passive"))
      (node (ref "U11F") (pin "4") (pinfunction "Y_4") (pintype "output"))
    )
    (net (code "143") (name "Net-(U10F-EN)") (class "Default")
      (node (ref "R20F") (pin "1") (pinfunction "1_1") (pintype "passive"))
      (node (ref "U10F") (pin "6") (pinfunction "EN_6") (pintype "input"))
    )
    (net (code "144") (name "Net-(U10F-FB)") (class "Default")
      (node (ref "R18F") (pin "1") (pinfunction "1_1") (pintype "passive"))
      (node (ref "R19F") (pin "2") (pinfunction "2_2") (pintype "passive"))
      (node (ref "U10F") (pin "1") (pinfunction "FB_1") (pintype "passive"))
    )
    (net (code "145") (name "P1.2V") (class "Default")
      (node (ref "C51F") (pin "1") (pinfunction "1_1") (pintype "passive"))
      (node (ref "C52F") (pin "1") (pinfunction "1_1") (pintype "passive"))
      (node (ref "C53F") (pin "1") (pinfunction "1_1") (pintype "passive"))
      (node (ref "C54F") (pin "1") (pinfunction "1_1") (pintype "passive"))
      (node (ref "C55F") (pin "1") (pinfunction "1_1") (pintype "passive"))
      (node (ref "C56F") (pin "1") (pinfunction "1_1") (pintype "passive"))
      (node (ref "C57F") (pin "1") (pinfunction "1_1") (pintype "passive"))
      (node (ref "C58F") (pin "1") (pinfunction "1_1") (pintype "passive"))
      (node (ref "C59F") (pin "1") (pinfunction "1_1") (pintype "passive"))
      (node (ref "C60F") (pin "2") (pinfunction "2_2") (pintype "passive"))
      (node (ref "C61F") (pin "1") (pinfunction "1_1") (pintype "passive"))
      (node (ref "C62F") (pin "2") (pinfunction "2_2") (pintype "passive"))
      (node (ref "C63F") (pin "2") (pinfunction "2_2") (pintype "passive"))
      (node (ref "L10F") (pin "2") (pinfunction "2_2") (pintype "passive"))
      (node (ref "R19F") (pin "1") (pinfunction "1_1") (pintype "passive"))
      (node (ref "U800") (pin "G7") (pinfunction "VCCINT_G7") (pintype "power_in"))
      (node (ref "U800") (pin "H11") (pinfunction "VCCINT_H11") (pintype "power_in"))
      (node (ref "U800") (pin "H9") (pinfunction "VCCINT_H9") (pintype "power_in"))
      (node (ref "U800") (pin "J10") (pinfunction "VCCINT_J10") (pintype "power_in"))
      (node (ref "U800") (pin "J8") (pinfunction "VCCINT_J8") (pintype "power_in"))
      (node (ref "U800") (pin "K11") (pinfunction "VCCINT_K11") (pintype "power_in"))
      (node (ref "U800") (pin "K9") (pinfunction "VCCINT_K9") (pintype "power_in"))
      (node (ref "U800") (pin "L10") (pinfunction "VCCINT_L10") (pintype "power_in"))
      (node (ref "U800") (pin "L8") (pinfunction "VCCINT_L8") (pintype "power_in"))
      (node (ref "U800") (pin "M12") (pinfunction "VCCINT_M12") (pintype "power_in"))
      (node (ref "U800") (pin "M7") (pinfunction "VCCINT_M7") (pintype "power_in"))
    )
    (net (code "146") (name "P3.3V_DELAYED") (class "Default")
      (node (ref "C10F") (pin "1") (pinfunction "1_1") (pintype "passive"))
      (node (ref "C11F") (pin "1") (pinfunction "1_1") (pintype "passive"))
      (node (ref "C12F") (pin "1") (pinfunction "1_1") (pintype "passive"))
      (node (ref "C13F") (pin "1") (pinfunction "1_1") (pintype "passive"))
      (node (ref "C14F") (pin "1") (pinfunction "1_1") (pintype "passive"))
      (node (ref "C15F") (pin "1") (pinfunction "1_1") (pintype "passive"))
      (node (ref "C16F") (pin "1") (pinfunction "1_1") (pintype "passive"))
      (node (ref "C17F") (pin "1") (pinfunction "1_1") (pintype "passive"))
      (node (ref "C18F") (pin "1") (pinfunction "1_1") (pintype "passive"))
      (node (ref "C19F") (pin "1") (pinfunction "1_1") (pintype "passive"))
      (node (ref "C20F") (pin "2") (pinfunction "2_2") (pintype "passive"))
      (node (ref "C21F") (pin "1") (pinfunction "1_1") (pintype "passive"))
      (node (ref "C22F") (pin "1") (pinfunction "1_1") (pintype "passive"))
      (node (ref "C23F") (pin "1") (pinfunction "1_1") (pintype "passive"))
      (node (ref "C24F") (pin "1") (pinfunction "1_1") (pintype "passive"))
      (node (ref "C25F") (pin "1") (pinfunction "1_1") (pintype "passive"))
      (node (ref "C26F") (pin "1") (pinfunction "1_1") (pintype "passive"))
      (node (ref "C27F") (pin "1") (pinfunction "1_1") (pintype "passive"))
      (node (ref "C28F") (pin "1") (pinfunction "1_1") (pintype "passive"))
      (node (ref "C29F") (pin "1") (pinfunction "1_1") (pintype "passive"))
      (node (ref "C30F") (pin "2") (pinfunction "2_2") (pintype "passive"))
      (node (ref "C31F") (pin "1") (pinfunction "1_1") (pintype "passive"))
      (node (ref "C32F") (pin "1") (pinfunction "1_1") (pintype "passive"))
      (node (ref "C33F") (pin "1") (pinfunction "1_1") (pintype "passive"))
      (node (ref "C34F") (pin "1") (pinfunction "1_1") (pintype "passive"))
      (node (ref "C35F") (pin "1") (pinfunction "1_1") (pintype "passive"))
      (node (ref "C36F") (pin "1") (pinfunction "1_1") (pintype "passive"))
      (node (ref "C37F") (pin "1") (pinfunction "1_1") (pintype "passive"))
      (node (ref "C38F") (pin "1") (pinfunction "1_1") (pintype "passive"))
      (node (ref "C39F") (pin "1") (pinfunction "1_1") (pintype "passive"))
      (node (ref "C40F") (pin "2") (pinfunction "2_2") (pintype "passive"))
      (node (ref "C41F") (pin "1") (pinfunction "1_1") (pintype "passive"))
      (node (ref "C42F") (pin "1") (pinfunction "1_1") (pintype "passive"))
      (node (ref "C43F") (pin "1") (pinfunction "1_1") (pintype "passive"))
      (node (ref "C44F") (pin "1") (pinfunction "1_1") (pintype "passive"))
      (node (ref "C45F") (pin "1") (pinfunction "1_1") (pintype "passive"))
      (node (ref "C46F") (pin "1") (pinfunction "1_1") (pintype "passive"))
      (node (ref "C47F") (pin "1") (pinfunction "1_1") (pintype "passive"))
      (node (ref "C48F") (pin "1") (pinfunction "1_1") (pintype "passive"))
      (node (ref "C49F") (pin "2") (pinfunction "2_2") (pintype "passive"))
      (node (ref "C50F") (pin "1") (pinfunction "1_1") (pintype "passive"))
      (node (ref "C64F") (pin "1") (pinfunction "1_1") (pintype "passive"))
      (node (ref "C66F") (pin "1") (pinfunction "1_1") (pintype "passive"))
      (node (ref "C67F") (pin "1") (pinfunction "1_1") (pintype "passive"))
      (node (ref "C73F") (pin "2") (pinfunction "2_2") (pintype "passive"))
      (node (ref "C75F") (pin "1") (pinfunction "1_1") (pintype "passive"))
      (node (ref "D20F") (pin "1") (pinfunction "K_1") (pintype "passive"))
      (node (ref "P10F") (pin "1") (pinfunction "1_1") (pintype "passive"))
      (node (ref "P14F") (pin "1") (pinfunction "1_1") (pintype "passive"))
      (node (ref "P14F") (pin "11") (pinfunction "11_11") (pintype "passive"))
      (node (ref "P14F") (pin "13") (pinfunction "13_13") (pintype "passive"))
      (node (ref "P14F") (pin "15") (pinfunction "15_15") (pintype "passive"))
      (node (ref "P14F") (pin "3") (pinfunction "3_3") (pintype "passive"))
      (node (ref "P14F") (pin "5") (pinfunction "5_5") (pintype "passive"))
      (node (ref "P14F") (pin "7") (pinfunction "7_7") (pintype "passive"))
      (node (ref "P14F") (pin "9") (pinfunction "9_9") (pintype "passive"))
      (node (ref "P_LI2C_WP") (pin "2") (pinfunction "2_2") (pintype "passive"))
      (node (ref "R11F") (pin "2") (pinfunction "2_2") (pintype "passive"))
      (node (ref "R13F") (pin "2") (pinfunction "2_2") (pintype "passive"))
      (node (ref "R14F") (pin "1") (pinfunction "1_1") (pintype "passive"))
      (node (ref "R16F") (pin "1") (pinfunction "1_1") (pintype "passive"))
      (node (ref "R21F") (pin "1") (pinfunction "1_1") (pintype "passive"))
      (node (ref "R22F") (pin "2") (pinfunction "2_2") (pintype "passive"))
      (node (ref "R25F") (pin "2") (pinfunction "2_2") (pintype "passive"))
      (node (ref "R28F") (pin "1") (pinfunction "1_1") (pintype "passive"))
      (node (ref "R29F") (pin "1") (pinfunction "1_1") (pintype "passive"))
      (node (ref "R30F") (pin "1") (pinfunction "1_1") (pintype "passive"))
      (node (ref "U11F") (pin "5") (pinfunction "Vcc_5") (pintype "power_in"))
      (node (ref "U12F") (pin "13") (pinfunction "VD_13") (pintype "power_in"))
      (node (ref "U13F") (pin "8") (pinfunction "VCC_8") (pintype "power_in"))
      (node (ref "U14F") (pin "8") (pinfunction "VCC_8") (pintype "power_in"))
      (node (ref "U800") (pin "B1") (pinfunction "VCCAUX_B1") (pintype "power_in"))
      (node (ref "U800") (pin "B10") (pinfunction "VCCO_0_B10") (pintype "power_in"))
      (node (ref "U800") (pin "B15") (pinfunction "VCCO_0_B15") (pintype "power_in"))
      (node (ref "U800") (pin "B17") (pinfunction "VCCAUX_B17") (pintype "power_in"))
      (node (ref "U800") (pin "B5") (pinfunction "VCCO_0_B5") (pintype "power_in"))
      (node (ref "U800") (pin "D13") (pinfunction "VCCO_0_D13") (pintype "power_in"))
      (node (ref "U800") (pin "D7") (pinfunction "VCCO_0_D7") (pintype "power_in"))
      (node (ref "U800") (pin "E10") (pinfunction "VCCO_0_E10") (pintype "power_in"))
      (node (ref "U800") (pin "E14") (pinfunction "VCCAUX_E14") (pintype "power_in"))
      (node (ref "U800") (pin "E17") (pinfunction "VCCO_1_E17") (pintype "power_in"))
      (node (ref "U800") (pin "E2") (pinfunction "VCCO_3_E2") (pintype "power_in"))
      (node (ref "U800") (pin "E5") (pinfunction "VCCAUX_E5") (pintype "power_in"))
      (node (ref "U800") (pin "E9") (pinfunction "VCCAUX_E9") (pintype "power_in"))
      (node (ref "U800") (pin "G10") (pinfunction "VCCAUX_G10") (pintype "power_in"))
      (node (ref "U800") (pin "G15") (pinfunction "VCCO_1_G15") (pintype "power_in"))
      (node (ref "U800") (pin "G4") (pinfunction "VCCO_3_G4") (pintype "power_in"))
      (node (ref "U800") (pin "J12") (pinfunction "VCCAUX_J12") (pintype "power_in"))
      (node (ref "U800") (pin "J14") (pinfunction "VCCO_1_J14") (pintype "power_in"))
      (node (ref "U800") (pin "J17") (pinfunction "VCCO_1_J17") (pintype "power_in"))
      (node (ref "U800") (pin "J2") (pinfunction "VCCO_3_J2") (pintype "power_in"))
      (node (ref "U800") (pin "J5") (pinfunction "VCCO_3_J5") (pintype "power_in"))
      (node (ref "U800") (pin "K7") (pinfunction "VCCAUX_K7") (pintype "power_in"))
      (node (ref "U800") (pin "M15") (pinfunction "VCCO_1_M15") (pintype "power_in"))
      (node (ref "U800") (pin "M4") (pinfunction "VCCO_3_M4") (pintype "power_in"))
      (node (ref "U800") (pin "M9") (pinfunction "VCCAUX_M9") (pintype "power_in"))
      (node (ref "U800") (pin "P10") (pinfunction "VCCAUX_P10") (pintype "power_in"))
      (node (ref "U800") (pin "P14") (pinfunction "VCCAUX_P14") (pintype "power_in"))
      (node (ref "U800") (pin "P5") (pinfunction "VCCAUX_P5") (pintype "power_in"))
      (node (ref "U800") (pin "P9") (pinfunction "VCCO_2_P9") (pintype "power_in"))
      (node (ref "U800") (pin "R12") (pinfunction "VCCO_2_R12") (pintype "power_in"))
      (node (ref "U800") (pin "R17") (pinfunction "VCCO_1_R17") (pintype "power_in"))
      (node (ref "U800") (pin "R2") (pinfunction "VCCO_3_R2") (pintype "power_in"))
      (node (ref "U800") (pin "R6") (pinfunction "VCCO_2_R6") (pintype "power_in"))
      (node (ref "U800") (pin "U14") (pinfunction "VCCO_2_U14") (pintype "power_in"))
      (node (ref "U800") (pin "U4") (pinfunction "VCCO_2_U4") (pintype "power_in"))
      (node (ref "U800") (pin "U9") (pinfunction "VCCO_2_U9") (pintype "power_in"))
    )
    (net (code "147") (name "P5.0V_DELAYED") (class "Default")
      (node (ref "C65F") (pin "1") (pinfunction "1_1") (pintype "passive"))
      (node (ref "C71F") (pin "1") (pinfunction "1_1") (pintype "passive"))
      (node (ref "P_PWM") (pin "2") (pinfunction "2_2") (pintype "passive"))
      (node (ref "R20F") (pin "2") (pinfunction "2_2") (pintype "passive"))
      (node (ref "U10F") (pin "4") (pinfunction "VIND_4") (pintype "power_in"))
      (node (ref "U10F") (pin "5") (pinfunction "VINA_5") (pintype "power_in"))
      (node (ref "U15F") (pin "1") (pinfunction "VIN_1") (pintype "input"))
      (node (ref "U15F") (pin "3") (pinfunction "ON/OFF_3") (pintype "input"))
    )
    (net (code "148") (name "VANA") (class "Default")
      (node (ref "C68F") (pin "1") (pinfunction "1_1") (pintype "passive"))
      (node (ref "C69F") (pin "1") (pinfunction "1_1") (pintype "passive"))
      (node (ref "C70F") (pin "1") (pinfunction "1_1") (pintype "passive"))
      (node (ref "C72F") (pin "2") (pinfunction "2_2") (pintype "passive"))
      (node (ref "D18F") (pin "1") (pinfunction "K_1") (pintype "passive"))
      (node (ref "P12F") (pin "1") (pinfunction "1_1") (pintype "passive"))
      (node (ref "P12F") (pin "11") (pinfunction "11_11") (pintype "passive"))
      (node (ref "P12F") (pin "13") (pinfunction "13_13") (pintype "passive"))
      (node (ref "P12F") (pin "15") (pinfunction "15_15") (pintype "passive"))
      (node (ref "P12F") (pin "3") (pinfunction "3_3") (pintype "passive"))
      (node (ref "P12F") (pin "5") (pinfunction "5_5") (pintype "passive"))
      (node (ref "P12F") (pin "7") (pinfunction "7_7") (pintype "passive"))
      (node (ref "P12F") (pin "9") (pinfunction "9_9") (pintype "passive"))
      (node (ref "U12F") (pin "2") (pinfunction "VA_2") (pintype "power_in"))
      (node (ref "U15F") (pin "5") (pinfunction "VOUT_5") (pintype "power_in"))
    )
    (net (code "149") (name "unconnected-(U15F-N{slash}C-Pad4)") (class "Default")
      (node (ref "U15F") (pin "4") (pinfunction "N/C_4") (pintype "passive"))
    )
    (net (code "150") (name "unconnected-(U800A-IO_L2P_0-PadB2)") (class "Default")
      (node (ref "U800") (pin "B2") (pinfunction "IO_L2P_0_B2") (pintype "bidirectional"))
    )
    (net (code "151") (name "unconnected-(U800A-IO_L3N_0-PadC6)") (class "Default")
      (node (ref "U800") (pin "C6") (pinfunction "IO_L3N_0_C6") (pintype "bidirectional"))
    )
    (net (code "152") (name "unconnected-(U800A-IO_L3P_0-PadD6)") (class "Default")
      (node (ref "U800") (pin "D6") (pinfunction "IO_L3P_0_D6") (pintype "bidirectional"))
    )
    (net (code "153") (name "unconnected-(U800A-IO_L66N_SCP0_0-PadA16)") (class "Default")
      (node (ref "U800") (pin "A16") (pinfunction "IO_L66N_SCP0_0_A16") (pintype "bidirectional"))
    )
    (net (code "154") (name "unconnected-(U800B-IO_L1P_A25_1-PadF15)") (class "Default")
      (node (ref "U800") (pin "F15") (pinfunction "IO_L1P_A25_1_F15") (pintype "bidirectional"))
    )
    (net (code "155") (name "unconnected-(U800B-IO_L32N_A16_M1A9_1-PadG13)") (class "Default")
      (node (ref "U800") (pin "G13") (pinfunction "IO_L32N_A16_M1A9_1_G13") (pintype "bidirectional"))
    )
    (net (code "156") (name "unconnected-(U800B-IO_L34N_A12_M1BA2_1-PadK13)") (class "Default")
      (node (ref "U800") (pin "K13") (pinfunction "IO_L34N_A12_M1BA2_1_K13") (pintype "bidirectional"))
    )
    (net (code "157") (name "unconnected-(U800B-IO_L34P_A13_M1WE_1-PadK12)") (class "Default")
      (node (ref "U800") (pin "K12") (pinfunction "IO_L34P_A13_M1WE_1_K12") (pintype "bidirectional"))
    )
    (net (code "158") (name "unconnected-(U800B-IO_L36N_A8_M1BA1_1-PadH14)") (class "Default")
      (node (ref "U800") (pin "H14") (pinfunction "IO_L36N_A8_M1BA1_1_H14") (pintype "bidirectional"))
    )
    (net (code "159") (name "unconnected-(U800B-IO_L36P_A9_M1BA0_1-PadH13)") (class "Default")
      (node (ref "U800") (pin "H13") (pinfunction "IO_L36P_A9_M1BA0_1_H13") (pintype "bidirectional"))
    )
    (net (code "160") (name "unconnected-(U800B-IO_L37P_A7_M1A0_1-PadH15)") (class "Default")
      (node (ref "U800") (pin "H15") (pinfunction "IO_L37P_A7_M1A0_1_H15") (pintype "bidirectional"))
    )
    (net (code "161") (name "unconnected-(U800B-IO_L39N_M1ODT_1-PadK14)") (class "Default")
      (node (ref "U800") (pin "K14") (pinfunction "IO_L39N_M1ODT_1_K14") (pintype "bidirectional"))
    )
    (net (code "162") (name "unconnected-(U800B-IO_L39P_M1A3_1-PadJ13)") (class "Default")
      (node (ref "U800") (pin "J13") (pinfunction "IO_L39P_M1A3_1_J13") (pintype "bidirectional"))
    )
    (net (code "163") (name "unconnected-(U800B-IO_L40N_GCLK10_M1A6_1-PadL13)") (class "Default")
      (node (ref "U800") (pin "L13") (pinfunction "IO_L40N_GCLK10_M1A6_1_L13") (pintype "bidirectional"))
    )
    (net (code "164") (name "unconnected-(U800B-IO_L40P_GCLK11_M1A5_1-PadL12)") (class "Default")
      (node (ref "U800") (pin "L12") (pinfunction "IO_L40P_GCLK11_M1A5_1_L12") (pintype "bidirectional"))
    )
    (net (code "165") (name "unconnected-(U800B-IO_L41P_GCLK9_IRDY1_M1RASN_1-PadK15)") (class "Default")
      (node (ref "U800") (pin "K15") (pinfunction "IO_L41P_GCLK9_IRDY1_M1RASN_1_K15") (pintype "bidirectional"))
    )
    (net (code "166") (name "unconnected-(U800B-IO_L44P_A3_M1DQ6_1-PadJ16)") (class "Default")
      (node (ref "U800") (pin "J16") (pinfunction "IO_L44P_A3_M1DQ6_1_J16") (pintype "bidirectional"))
    )
    (net (code "167") (name "unconnected-(U800B-IO_L46N_FOE_B_M1DQ3_1-PadL18)") (class "Default")
      (node (ref "U800") (pin "L18") (pinfunction "IO_L46N_FOE_B_M1DQ3_1_L18") (pintype "bidirectional"))
    )
    (net (code "168") (name "unconnected-(U800B-IO_L46P_FCS_B_M1DQ2_1-PadL17)") (class "Default")
      (node (ref "U800") (pin "L17") (pinfunction "IO_L46P_FCS_B_M1DQ2_1_L17") (pintype "bidirectional"))
    )
    (net (code "169") (name "unconnected-(U800B-IO_L47N_LDC_M1DQ1_1-PadM18)") (class "Default")
      (node (ref "U800") (pin "M18") (pinfunction "IO_L47N_LDC_M1DQ1_1_M18") (pintype "bidirectional"))
    )
    (net (code "170") (name "unconnected-(U800B-IO_L47P_FWE_B_M1DQ0_1-PadM16)") (class "Default")
      (node (ref "U800") (pin "M16") (pinfunction "IO_L47P_FWE_B_M1DQ0_1_M16") (pintype "bidirectional"))
    )
    (net (code "171") (name "unconnected-(U800B-IO_L50N_M1UDQSN_1-PadN16)") (class "Default")
      (node (ref "U800") (pin "N16") (pinfunction "IO_L50N_M1UDQSN_1_N16") (pintype "bidirectional"))
    )
    (net (code "172") (name "unconnected-(U800B-IO_L50P_M1UDQS_1-PadN15)") (class "Default")
      (node (ref "U800") (pin "N15") (pinfunction "IO_L50P_M1UDQS_1_N15") (pintype "bidirectional"))
    )
    (net (code "173") (name "unconnected-(U800B-IO_L51N_M1DQ13_1-PadT18)") (class "Default")
      (node (ref "U800") (pin "T18") (pinfunction "IO_L51N_M1DQ13_1_T18") (pintype "bidirectional"))
    )
    (net (code "174") (name "unconnected-(U800B-IO_L51P_M1DQ12_1-PadT17)") (class "Default")
      (node (ref "U800") (pin "T17") (pinfunction "IO_L51P_M1DQ12_1_T17") (pintype "bidirectional"))
    )
    (net (code "175") (name "unconnected-(U800B-IO_L53N_VREF_1-PadN14)") (class "Default")
      (node (ref "U800") (pin "N14") (pinfunction "IO_L53N_VREF_1_N14") (pintype "bidirectional"))
    )
    (net (code "176") (name "unconnected-(U800B-IO_L53P_1-PadM14)") (class "Default")
      (node (ref "U800") (pin "M14") (pinfunction "IO_L53P_1_M14") (pintype "bidirectional"))
    )
    (net (code "177") (name "unconnected-(U800B-IO_L61N_1-PadM13)") (class "Default")
      (node (ref "U800") (pin "M13") (pinfunction "IO_L61N_1_M13") (pintype "bidirectional"))
    )
    (net (code "178") (name "unconnected-(U800B-IO_L61P_1-PadL14)") (class "Default")
      (node (ref "U800") (pin "L14") (pinfunction "IO_L61P_1_L14") (pintype "bidirectional"))
    )
    (net (code "179") (name "unconnected-(U800B-IO_L74N_DOUT_BUSY_1-PadP16)") (class "Default")
      (node (ref "U800") (pin "P16") (pinfunction "IO_L74N_DOUT_BUSY_1_P16") (pintype "bidirectional"))
    )
    (net (code "180") (name "unconnected-(U800B-IO_L74P_AWAKE_1-PadP15)") (class "Default")
      (node (ref "U800") (pin "P15") (pinfunction "IO_L74P_AWAKE_1_P15") (pintype "bidirectional"))
    )
    (net (code "181") (name "unconnected-(U800C-IO_L2N_CMPMOSI_2-PadV16)") (class "Default")
      (node (ref "U800") (pin "V16") (pinfunction "IO_L2N_CMPMOSI_2_V16") (pintype "bidirectional"))
    )
    (net (code "182") (name "unconnected-(U800C-IO_L3N_MOSI_CSI_B_MISO0_2-PadT13)") (class "Default")
      (node (ref "U800") (pin "T13") (pinfunction "IO_L3N_MOSI_CSI_B_MISO0_2_T13") (pintype "bidirectional"))
    )
    (net (code "183") (name "unconnected-(U800C-IO_L12N_D2_MISO3_2-PadV14)") (class "Default")
      (node (ref "U800") (pin "V14") (pinfunction "IO_L12N_D2_MISO3_2_V14") (pintype "bidirectional"))
    )
    (net (code "184") (name "unconnected-(U800C-IO_L12P_D1_MISO2_2-PadT14)") (class "Default")
      (node (ref "U800") (pin "T14") (pinfunction "IO_L12P_D1_MISO2_2_T14") (pintype "bidirectional"))
    )
    (net (code "185") (name "unconnected-(U800C-IO_L13N_D10_2-PadP12)") (class "Default")
      (node (ref "U800") (pin "P12") (pinfunction "IO_L13N_D10_2_P12") (pintype "bidirectional"))
    )
    (net (code "186") (name "unconnected-(U800C-IO_L14N_D12_2-PadV13)") (class "Default")
      (node (ref "U800") (pin "V13") (pinfunction "IO_L14N_D12_2_V13") (pintype "bidirectional"))
    )
    (net (code "187") (name "unconnected-(U800C-IO_L14P_D11_2-PadU13)") (class "Default")
      (node (ref "U800") (pin "U13") (pinfunction "IO_L14P_D11_2_U13") (pintype "bidirectional"))
    )
    (net (code "188") (name "unconnected-(U800C-IO_L16N_VREF_2-PadT11)") (class "Default")
      (node (ref "U800") (pin "T11") (pinfunction "IO_L16N_VREF_2_T11") (pintype "bidirectional"))
    )
    (net (code "189") (name "unconnected-(U800C-IO_L16P_2-PadR11)") (class "Default")
      (node (ref "U800") (pin "R11") (pinfunction "IO_L16P_2_R11") (pintype "bidirectional"))
    )
    (net (code "190") (name "unconnected-(U800C-IO_L23N_2-PadV11)") (class "Default")
      (node (ref "U800") (pin "V11") (pinfunction "IO_L23N_2_V11") (pintype "bidirectional"))
    )
    (net (code "191") (name "unconnected-(U800C-IO_L23P_2-PadU11)") (class "Default")
      (node (ref "U800") (pin "U11") (pinfunction "IO_L23P_2_U11") (pintype "bidirectional"))
    )
    (net (code "192") (name "unconnected-(U800C-IO_L29N_GCLK2_2-PadT10)") (class "Default")
      (node (ref "U800") (pin "T10") (pinfunction "IO_L29N_GCLK2_2_T10") (pintype "bidirectional"))
    )
    (net (code "193") (name "unconnected-(U800C-IO_L29P_GCLK3_2-PadR10)") (class "Default")
      (node (ref "U800") (pin "R10") (pinfunction "IO_L29P_GCLK3_2_R10") (pintype "bidirectional"))
    )
    (net (code "194") (name "unconnected-(U800C-IO_L30N_GCLK0_USERCCLK_2-PadV10)") (class "Default")
      (node (ref "U800") (pin "V10") (pinfunction "IO_L30N_GCLK0_USERCCLK_2_V10") (pintype "bidirectional"))
    )
    (net (code "195") (name "unconnected-(U800C-IO_L30P_GCLK1_D13_2-PadU10)") (class "Default")
      (node (ref "U800") (pin "U10") (pinfunction "IO_L30P_GCLK1_D13_2_U10") (pintype "bidirectional"))
    )
    (net (code "196") (name "unconnected-(U800C-IO_L31N_GCLK30_D15_2-PadT8)") (class "Default")
      (node (ref "U800") (pin "T8") (pinfunction "IO_L31N_GCLK30_D15_2_T8") (pintype "bidirectional"))
    )
    (net (code "197") (name "unconnected-(U800C-IO_L31P_GCLK31_D14_2-PadR8)") (class "Default")
      (node (ref "U800") (pin "R8") (pinfunction "IO_L31P_GCLK31_D14_2_R8") (pintype "bidirectional"))
    )
    (net (code "198") (name "unconnected-(U800C-IO_L32N_GCLK28_2-PadV9)") (class "Default")
      (node (ref "U800") (pin "V9") (pinfunction "IO_L32N_GCLK28_2_V9") (pintype "bidirectional"))
    )
    (net (code "199") (name "unconnected-(U800C-IO_L32P_GCLK29_2-PadT9)") (class "Default")
      (node (ref "U800") (pin "T9") (pinfunction "IO_L32P_GCLK29_2_T9") (pintype "bidirectional"))
    )
    (net (code "200") (name "unconnected-(U800C-IO_L41N_VREF_2-PadV8)") (class "Default")
      (node (ref "U800") (pin "V8") (pinfunction "IO_L41N_VREF_2_V8") (pintype "bidirectional"))
    )
    (net (code "201") (name "unconnected-(U800C-IO_L41P_2-PadU8)") (class "Default")
      (node (ref "U800") (pin "U8") (pinfunction "IO_L41P_2_U8") (pintype "bidirectional"))
    )
    (net (code "202") (name "unconnected-(U800C-IO_L43N_2-PadV7)") (class "Default")
      (node (ref "U800") (pin "V7") (pinfunction "IO_L43N_2_V7") (pintype "bidirectional"))
    )
    (net (code "203") (name "unconnected-(U800C-IO_L43P_2-PadU7)") (class "Default")
      (node (ref "U800") (pin "U7") (pinfunction "IO_L43P_2_U7") (pintype "bidirectional"))
    )
    (net (code "204") (name "unconnected-(U800C-IO_L45N_2-PadV6)") (class "Default")
      (node (ref "U800") (pin "V6") (pinfunction "IO_L45N_2_V6") (pintype "bidirectional"))
    )
    (net (code "205") (name "unconnected-(U800C-IO_L45P_2-PadT6)") (class "Default")
      (node (ref "U800") (pin "T6") (pinfunction "IO_L45P_2_T6") (pintype "bidirectional"))
    )
    (net (code "206") (name "unconnected-(U800C-IO_L46N_2-PadT7)") (class "Default")
      (node (ref "U800") (pin "T7") (pinfunction "IO_L46N_2_T7") (pintype "bidirectional"))
    )
    (net (code "207") (name "unconnected-(U800C-IO_L46P_2-PadR7)") (class "Default")
      (node (ref "U800") (pin "R7") (pinfunction "IO_L46P_2_R7") (pintype "bidirectional"))
    )
    (net (code "208") (name "unconnected-(U800C-IO_L48N_RDWR_B_VREF_2-PadT5)") (class "Default")
      (node (ref "U800") (pin "T5") (pinfunction "IO_L48N_RDWR_B_VREF_2_T5") (pintype "bidirectional"))
    )
    (net (code "209") (name "unconnected-(U800C-IO_L48P_D7_2-PadR5)") (class "Default")
      (node (ref "U800") (pin "R5") (pinfunction "IO_L48P_D7_2_R5") (pintype "bidirectional"))
    )
    (net (code "210") (name "unconnected-(U800C-IO_L49N_D4_2-PadV5)") (class "Default")
      (node (ref "U800") (pin "V5") (pinfunction "IO_L49N_D4_2_V5") (pintype "bidirectional"))
    )
    (net (code "211") (name "unconnected-(U800C-IO_L49P_D3_2-PadU5)") (class "Default")
      (node (ref "U800") (pin "U5") (pinfunction "IO_L49P_D3_2_U5") (pintype "bidirectional"))
    )
    (net (code "212") (name "unconnected-(U800C-IO_L62N_D6_2-PadT3)") (class "Default")
      (node (ref "U800") (pin "T3") (pinfunction "IO_L62N_D6_2_T3") (pintype "bidirectional"))
    )
    (net (code "213") (name "unconnected-(U800C-IO_L62P_D5_2-PadR3)") (class "Default")
      (node (ref "U800") (pin "R3") (pinfunction "IO_L62P_D5_2_R3") (pintype "bidirectional"))
    )
    (net (code "214") (name "unconnected-(U800C-IO_L63N_2-PadV4)") (class "Default")
      (node (ref "U800") (pin "V4") (pinfunction "IO_L63N_2_V4") (pintype "bidirectional"))
    )
    (net (code "215") (name "unconnected-(U800C-IO_L63P_2-PadT4)") (class "Default")
      (node (ref "U800") (pin "T4") (pinfunction "IO_L63P_2_T4") (pintype "bidirectional"))
    )
    (net (code "216") (name "unconnected-(U800C-IO_L64N_D9_2-PadP6)") (class "Default")
      (node (ref "U800") (pin "P6") (pinfunction "IO_L64N_D9_2_P6") (pintype "bidirectional"))
    )
    (net (code "217") (name "unconnected-(U800C-IO_L64P_D8_2-PadN5)") (class "Default")
      (node (ref "U800") (pin "N5") (pinfunction "IO_L64P_D8_2_N5") (pintype "bidirectional"))
    )
    (net (code "218") (name "unconnected-(U800C-IO_L65N_CSO_B_2-PadV3)") (class "Default")
      (node (ref "U800") (pin "V3") (pinfunction "IO_L65N_CSO_B_2_V3") (pintype "bidirectional"))
    )
    (net (code "219") (name "unconnected-(U800D-IO_L31N_VREF_3-PadM5)") (class "Default")
      (node (ref "U800") (pin "M5") (pinfunction "IO_L31N_VREF_3_M5") (pintype "bidirectional"))
    )
    (net (code "220") (name "unconnected-(U800D-IO_L31P_3-PadL6)") (class "Default")
      (node (ref "U800") (pin "L6") (pinfunction "IO_L31P_3_L6") (pintype "bidirectional"))
    )
    (net (code "221") (name "unconnected-(U800D-IO_L36N_M3DQ9_3-PadM1)") (class "Default")
      (node (ref "U800") (pin "M1") (pinfunction "IO_L36N_M3DQ9_3_M1") (pintype "bidirectional"))
    )
    (net (code "222") (name "unconnected-(U800D-IO_L36P_M3DQ8_3-PadM3)") (class "Default")
      (node (ref "U800") (pin "M3") (pinfunction "IO_L36P_M3DQ8_3_M3") (pintype "bidirectional"))
    )
    (net (code "223") (name "unconnected-(U800D-IO_L37N_M3DQ1_3-PadL1)") (class "Default")
      (node (ref "U800") (pin "L1") (pinfunction "IO_L37N_M3DQ1_3_L1") (pintype "bidirectional"))
    )
    (net (code "224") (name "unconnected-(U800D-IO_L37P_M3DQ0_3-PadL2)") (class "Default")
      (node (ref "U800") (pin "L2") (pinfunction "IO_L37P_M3DQ0_3_L2") (pintype "bidirectional"))
    )
    (net (code "225") (name "unconnected-(U800D-IO_L38P_M3DQ2_3-PadK2)") (class "Default")
      (node (ref "U800") (pin "K2") (pinfunction "IO_L38P_M3DQ2_3_K2") (pintype "bidirectional"))
    )
    (net (code "226") (name "unconnected-(U800D-IO_L39N_M3LDQSN_3-PadL3)") (class "Default")
      (node (ref "U800") (pin "L3") (pinfunction "IO_L39N_M3LDQSN_3_L3") (pintype "bidirectional"))
    )
    (net (code "227") (name "unconnected-(U800D-IO_L39P_M3LDQS_3-PadL4)") (class "Default")
      (node (ref "U800") (pin "L4") (pinfunction "IO_L39P_M3LDQS_3_L4") (pintype "bidirectional"))
    )
    (net (code "228") (name "unconnected-(U800D-IO_L40N_M3DQ7_3-PadJ1)") (class "Default")
      (node (ref "U800") (pin "J1") (pinfunction "IO_L40N_M3DQ7_3_J1") (pintype "bidirectional"))
    )
    (net (code "229") (name "unconnected-(U800D-IO_L40P_M3DQ6_3-PadJ3)") (class "Default")
      (node (ref "U800") (pin "J3") (pinfunction "IO_L40P_M3DQ6_3_J3") (pintype "bidirectional"))
    )
    (net (code "230") (name "unconnected-(U800D-IO_L41N_GCLK26_M3DQ5_3-PadH1)") (class "Default")
      (node (ref "U800") (pin "H1") (pinfunction "IO_L41N_GCLK26_M3DQ5_3_H1") (pintype "bidirectional"))
    )
    (net (code "231") (name "unconnected-(U800D-IO_L41P_GCLK27_M3DQ4_3-PadH2)") (class "Default")
      (node (ref "U800") (pin "H2") (pinfunction "IO_L41P_GCLK27_M3DQ4_3_H2") (pintype "bidirectional"))
    )
    (net (code "232") (name "unconnected-(U800D-IO_L42N_GCLK24_M3LDM_3-PadK3)") (class "Default")
      (node (ref "U800") (pin "K3") (pinfunction "IO_L42N_GCLK24_M3LDM_3_K3") (pintype "bidirectional"))
    )
    (net (code "233") (name "unconnected-(U800D-IO_L42P_GCLK25_TRDY2_M3UDM_3-PadK4)") (class "Default")
      (node (ref "U800") (pin "K4") (pinfunction "IO_L42P_GCLK25_TRDY2_M3UDM_3_K4") (pintype "bidirectional"))
    )
    (net (code "234") (name "unconnected-(U800D-IO_L43N_GCLK22_IRDY2_M3CASN_3-PadK5)") (class "Default")
      (node (ref "U800") (pin "K5") (pinfunction "IO_L43N_GCLK22_IRDY2_M3CASN_3_K5") (pintype "bidirectional"))
    )
    (net (code "235") (name "unconnected-(U800D-IO_L43P_GCLK23_M3RASN_3-PadL5)") (class "Default")
      (node (ref "U800") (pin "L5") (pinfunction "IO_L43P_GCLK23_M3RASN_3_L5") (pintype "bidirectional"))
    )
    (net (code "236") (name "unconnected-(U800D-IO_L44N_GCLK20_M3A6_3-PadH3)") (class "Default")
      (node (ref "U800") (pin "H3") (pinfunction "IO_L44N_GCLK20_M3A6_3_H3") (pintype "bidirectional"))
    )
    (net (code "237") (name "unconnected-(U800D-IO_L44P_GCLK21_M3A5_3-PadH4)") (class "Default")
      (node (ref "U800") (pin "H4") (pinfunction "IO_L44P_GCLK21_M3A5_3_H4") (pintype "bidirectional"))
    )
    (net (code "238") (name "unconnected-(U800D-IO_L45N_M3ODT_3-PadK6)") (class "Default")
      (node (ref "U800") (pin "K6") (pinfunction "IO_L45N_M3ODT_3_K6") (pintype "bidirectional"))
    )
    (net (code "239") (name "unconnected-(U800D-IO_L45P_M3A3_3-PadL7)") (class "Default")
      (node (ref "U800") (pin "L7") (pinfunction "IO_L45P_M3A3_3_L7") (pintype "bidirectional"))
    )
    (net (code "240") (name "unconnected-(U800D-IO_L47N_M3A1_3-PadJ6)") (class "Default")
      (node (ref "U800") (pin "J6") (pinfunction "IO_L47N_M3A1_3_J6") (pintype "bidirectional"))
    )
    (net (code "241") (name "unconnected-(U800D-IO_L47P_M3A0_3-PadJ7)") (class "Default")
      (node (ref "U800") (pin "J7") (pinfunction "IO_L47P_M3A0_3_J7") (pintype "bidirectional"))
    )
    (net (code "242") (name "unconnected-(U800D-IO_L48N_M3BA1_3-PadF1)") (class "Default")
      (node (ref "U800") (pin "F1") (pinfunction "IO_L48N_M3BA1_3_F1") (pintype "bidirectional"))
    )
    (net (code "243") (name "unconnected-(U800D-IO_L48P_M3BA0_3-PadF2)") (class "Default")
      (node (ref "U800") (pin "F2") (pinfunction "IO_L48P_M3BA0_3_F2") (pintype "bidirectional"))
    )
    (net (code "244") (name "unconnected-(U800D-IO_L49N_M3A2_3-PadH5)") (class "Default")
      (node (ref "U800") (pin "H5") (pinfunction "IO_L49N_M3A2_3_H5") (pintype "bidirectional"))
    )
    (net (code "245") (name "unconnected-(U800D-IO_L49P_M3A7_3-PadH6)") (class "Default")
      (node (ref "U800") (pin "H6") (pinfunction "IO_L49P_M3A7_3_H6") (pintype "bidirectional"))
    )
    (net (code "246") (name "unconnected-(U800D-IO_L51N_M3A4_3-PadF3)") (class "Default")
      (node (ref "U800") (pin "F3") (pinfunction "IO_L51N_M3A4_3_F3") (pintype "bidirectional"))
    )
    (net (code "247") (name "unconnected-(U800D-IO_L51P_M3A10_3-PadF4)") (class "Default")
      (node (ref "U800") (pin "F4") (pinfunction "IO_L51P_M3A10_3_F4") (pintype "bidirectional"))
    )
    (net (code "248") (name "unconnected-(U800D-IO_L53N_M3A12_3-PadG6)") (class "Default")
      (node (ref "U800") (pin "G6") (pinfunction "IO_L53N_M3A12_3_G6") (pintype "bidirectional"))
    )
    (net (code "249") (name "unconnected-(U800D-IO_L53P_M3CKE_3-PadH7)") (class "Default")
      (node (ref "U800") (pin "H7") (pinfunction "IO_L53P_M3CKE_3_H7") (pintype "bidirectional"))
    )
    (net (code "250") (name "unconnected-(U800D-IO_L55N_M3A14_3-PadF5)") (class "Default")
      (node (ref "U800") (pin "F5") (pinfunction "IO_L55N_M3A14_3_F5") (pintype "bidirectional"))
    )
    (net (code "251") (name "unconnected-(U800D-IO_L55P_M3A13_3-PadF6)") (class "Default")
      (node (ref "U800") (pin "F6") (pinfunction "IO_L55P_M3A13_3_F6") (pintype "bidirectional"))
    )
    (net (code "252") (name "unconnected-(U800E-CMPCS_B_2-PadP13)") (class "Default")
      (node (ref "U800") (pin "P13") (pinfunction "CMPCS_B_2_P13") (pintype "input+no_connect"))
    )
    (net (code "253") (name "unconnected-(U800H-NC-PadA13)") (class "Default")
      (node (ref "U800") (pin "A13") (pinfunction "NC_A13") (pintype "passive"))
    )
    (net (code "254") (name "unconnected-(U800H-NC-PadC12)") (class "Default")
      (node (ref "U800") (pin "C12") (pinfunction "NC_C12") (pintype "passive"))
    )
    (net (code "255") (name "unconnected-(U800H-NC-PadC13)") (class "Default")
      (node (ref "U800") (pin "C13") (pinfunction "NC_C13") (pintype "passive"))
    )
    (net (code "256") (name "unconnected-(U800H-NC-PadD12)") (class "Default")
      (node (ref "U800") (pin "D12") (pinfunction "NC_D12") (pintype "passive"))
    )
    (net (code "257") (name "unconnected-(U800H-NC-PadE6)") (class "Default")
      (node (ref "U800") (pin "E6") (pinfunction "NC_E6") (pintype "passive"))
    )
    (net (code "258") (name "unconnected-(U800H-NC-PadE7)") (class "Default")
      (node (ref "U800") (pin "E7") (pinfunction "NC_E7") (pintype "passive"))
    )
    (net (code "259") (name "unconnected-(U800H-NC-PadE8)") (class "Default")
      (node (ref "U800") (pin "E8") (pinfunction "NC_E8") (pintype "passive"))
    )
    (net (code "260") (name "unconnected-(U800H-NC-PadE11)") (class "Default")
      (node (ref "U800") (pin "E11") (pinfunction "NC_E11") (pintype "passive"))
    )
    (net (code "261") (name "unconnected-(U800H-NC-PadE12)") (class "Default")
      (node (ref "U800") (pin "E12") (pinfunction "NC_E12") (pintype "passive"))
    )
    (net (code "262") (name "unconnected-(U800H-NC-PadF7)") (class "Default")
      (node (ref "U800") (pin "F7") (pinfunction "NC_F7") (pintype "passive"))
    )
    (net (code "263") (name "unconnected-(U800H-NC-PadF8)") (class "Default")
      (node (ref "U800") (pin "F8") (pinfunction "NC_F8") (pintype "passive"))
    )
    (net (code "264") (name "unconnected-(U800H-NC-PadF10)") (class "Default")
      (node (ref "U800") (pin "F10") (pinfunction "NC_F10") (pintype "passive"))
    )
    (net (code "265") (name "unconnected-(U800H-NC-PadF11)") (class "Default")
      (node (ref "U800") (pin "F11") (pinfunction "NC_F11") (pintype "passive"))
    )
    (net (code "266") (name "unconnected-(U800H-NC-PadF12)") (class "Default")
      (node (ref "U800") (pin "F12") (pinfunction "NC_F12") (pintype "passive"))
    )
    (net (code "267") (name "unconnected-(U800H-NC-PadG8)") (class "Default")
      (node (ref "U800") (pin "G8") (pinfunction "NC_G8") (pintype "passive"))
    )
    (net (code "268") (name "unconnected-(U800H-NC-PadG11)") (class "Default")
      (node (ref "U800") (pin "G11") (pinfunction "NC_G11") (pintype "passive"))
    )
    (net (code "269") (name "unconnected-(U800H-NC-PadM8)") (class "Default")
      (node (ref "U800") (pin "M8") (pinfunction "NC_M8") (pintype "passive"))
    )
    (net (code "270") (name "unconnected-(U800H-NC-PadM10)") (class "Default")
      (node (ref "U800") (pin "M10") (pinfunction "NC_M10") (pintype "passive"))
    )
    (net (code "271") (name "unconnected-(U800H-NC-PadM11)") (class "Default")
      (node (ref "U800") (pin "M11") (pinfunction "NC_M11") (pintype "passive"))
    )
    (net (code "272") (name "unconnected-(U800H-NC-PadN6)") (class "Default")
      (node (ref "U800") (pin "N6") (pinfunction "NC_N6") (pintype "passive"))
    )
    (net (code "273") (name "unconnected-(U800H-NC-PadN7)") (class "Default")
      (node (ref "U800") (pin "N7") (pinfunction "NC_N7") (pintype "passive"))
    )
    (net (code "274") (name "unconnected-(U800H-NC-PadN8)") (class "Default")
      (node (ref "U800") (pin "N8") (pinfunction "NC_N8") (pintype "passive"))
    )
    (net (code "275") (name "unconnected-(U800H-NC-PadN9)") (class "Default")
      (node (ref "U800") (pin "N9") (pinfunction "NC_N9") (pintype "passive"))
    )
    (net (code "276") (name "unconnected-(U800H-NC-PadN10)") (class "Default")
      (node (ref "U800") (pin "N10") (pinfunction "NC_N10") (pintype "passive"))
    )
    (net (code "277") (name "unconnected-(U800H-NC-PadN11)") (class "Default")
      (node (ref "U800") (pin "N11") (pinfunction "NC_N11") (pintype "passive"))
    )
    (net (code "278") (name "unconnected-(U800H-NC-PadP7)") (class "Default")
      (node (ref "U800") (pin "P7") (pinfunction "NC_P7") (pintype "passive"))
    )
    (net (code "279") (name "unconnected-(U800H-NC-PadP8)") (class "Default")
      (node (ref "U800") (pin "P8") (pinfunction "NC_P8") (pintype "passive"))
    )
    (net (code "280") (name "unconnected-(U800H-NC-PadP11)") (class "Default")
      (node (ref "U800") (pin "P11") (pinfunction "NC_P11") (pintype "passive"))
    )
    (net (code "281") (name "unconnected-(U800H-NC-PadT12)") (class "Default")
      (node (ref "U800") (pin "T12") (pinfunction "NC_T12") (pintype "passive"))
    )
    (net (code "282") (name "unconnected-(U800H-NC-PadU15)") (class "Default")
      (node (ref "U800") (pin "U15") (pinfunction "NC_U15") (pintype "passive"))
    )
    (net (code "283") (name "unconnected-(U800H-NC-PadV12)") (class "Default")
      (node (ref "U800") (pin "V12") (pinfunction "NC_V12") (pintype "passive"))
    )
    (net (code "284") (name "unconnected-(U800H-NC-PadV15)") (class "Default")
      (node (ref "U800") (pin "V15") (pinfunction "NC_V15") (pintype "passive"))
    )
  )
)
